# regulator_plus_switch_multi_no_rdbk.net
KiCad netlist of a schematic drawn in EAGLE
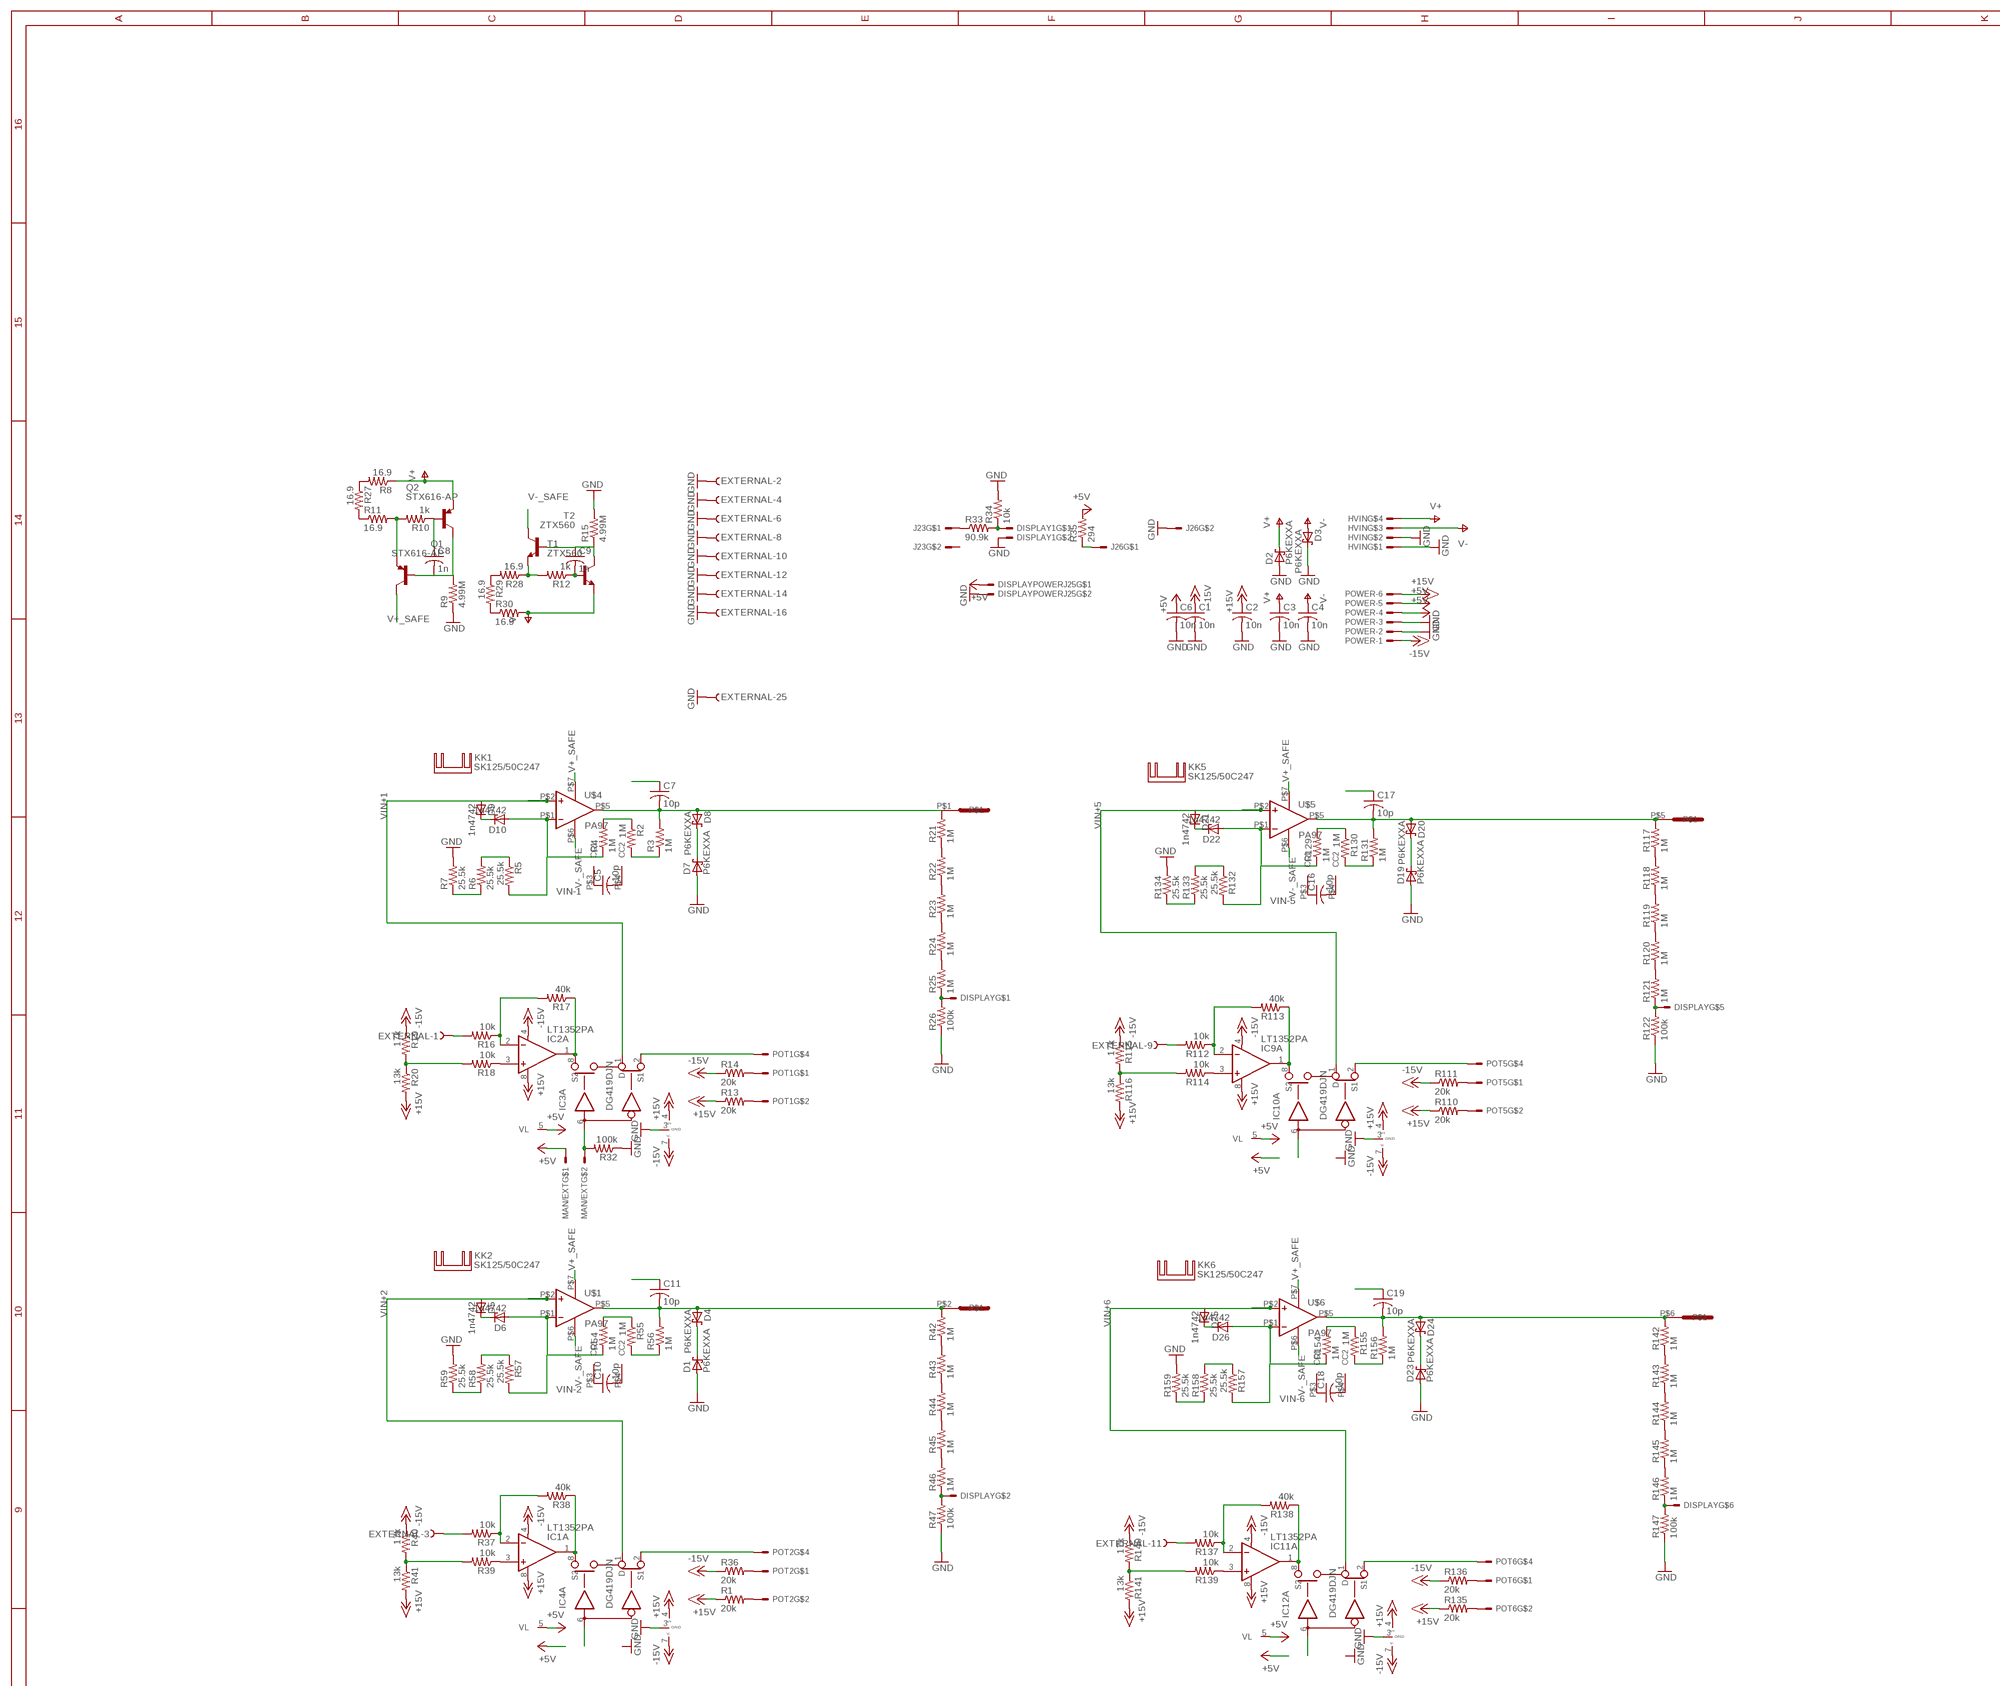
[diagram p0: schematic, sheet 1, part 1 of 2]
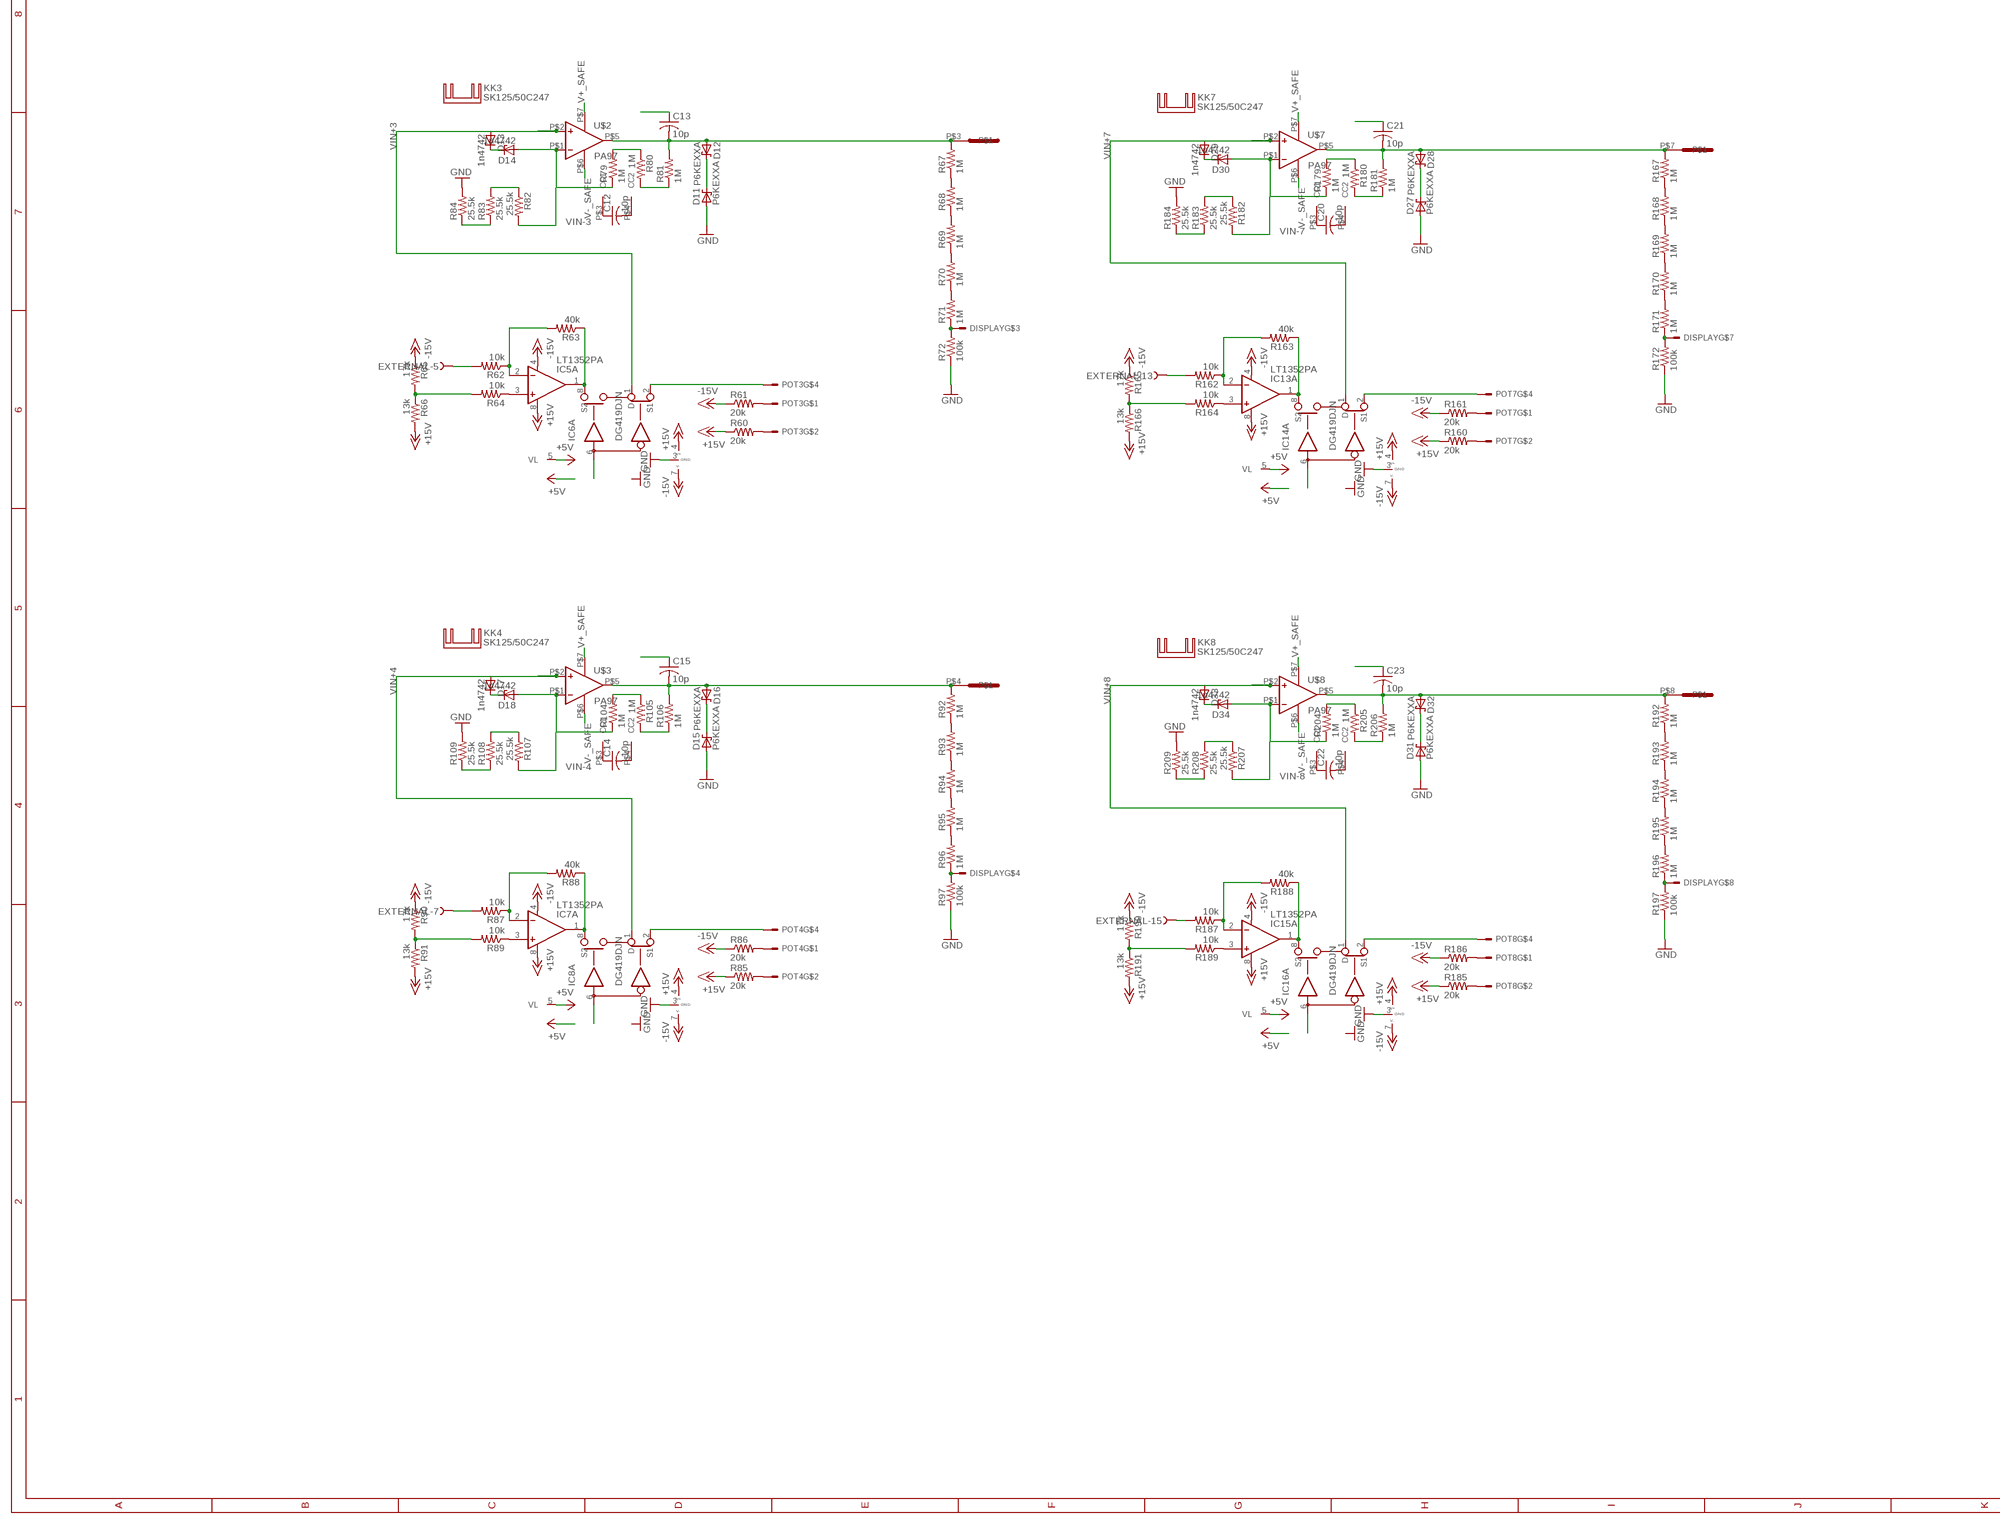
[diagram p1: schematic, sheet 1, part 2 of 2]

(export (version "E")
  (design (tool "Eeschema 10.0.6"))
  (components
    (comp (ref "C1")
      (value "10n")
      (footprint "eagle-import:C075-032X103")
      (libsource (lib "eagle-import") (part "C-US075-032X103"))
    )
    (comp (ref "C2")
      (value "10n")
      (footprint "eagle-import:C075-032X103")
      (libsource (lib "eagle-import") (part "C-US075-032X103"))
    )
    (comp (ref "C3")
      (value "10n")
      (footprint "eagle-import:C075-032X103")
      (libsource (lib "eagle-import") (part "C-US075-032X103"))
    )
    (comp (ref "C4")
      (value "10n")
      (footprint "eagle-import:C075-032X103")
      (libsource (lib "eagle-import") (part "C-US075-032X103"))
    )
    (comp (ref "C5")
      (value "10p")
      (footprint "eagle-import:C075-032X103")
      (libsource (lib "eagle-import") (part "C-US075-032X103"))
    )
    (comp (ref "C6")
      (value "10n")
      (footprint "eagle-import:C075-032X103")
      (libsource (lib "eagle-import") (part "C-US075-032X103"))
    )
    (comp (ref "C7")
      (value "10p")
      (footprint "eagle-import:C075-032X103")
      (libsource (lib "eagle-import") (part "C-US075-032X103"))
    )
    (comp (ref "C8")
      (value "1n")
      (footprint "eagle-import:C075-032X103")
      (libsource (lib "eagle-import") (part "C-US075-032X103"))
    )
    (comp (ref "C9")
      (value "1n")
      (footprint "eagle-import:C075-032X103")
      (libsource (lib "eagle-import") (part "C-US075-032X103"))
    )
    (comp (ref "C10")
      (value "10p")
      (footprint "eagle-import:C075-032X103")
      (libsource (lib "eagle-import") (part "C-US075-032X103"))
    )
    (comp (ref "C11")
      (value "10p")
      (footprint "eagle-import:C075-032X103")
      (libsource (lib "eagle-import") (part "C-US075-032X103"))
    )
    (comp (ref "C12")
      (value "10p")
      (footprint "eagle-import:C075-032X103")
      (libsource (lib "eagle-import") (part "C-US075-032X103"))
    )
    (comp (ref "C13")
      (value "10p")
      (footprint "eagle-import:C075-032X103")
      (libsource (lib "eagle-import") (part "C-US075-032X103"))
    )
    (comp (ref "C14")
      (value "10p")
      (footprint "eagle-import:C075-032X103")
      (libsource (lib "eagle-import") (part "C-US075-032X103"))
    )
    (comp (ref "C15")
      (value "10p")
      (footprint "eagle-import:C075-032X103")
      (libsource (lib "eagle-import") (part "C-US075-032X103"))
    )
    (comp (ref "C16")
      (value "10p")
      (footprint "eagle-import:C075-032X103")
      (libsource (lib "eagle-import") (part "C-US075-032X103"))
    )
    (comp (ref "C17")
      (value "10p")
      (footprint "eagle-import:C075-032X103")
      (libsource (lib "eagle-import") (part "C-US075-032X103"))
    )
    (comp (ref "C18")
      (value "10p")
      (footprint "eagle-import:C075-032X103")
      (libsource (lib "eagle-import") (part "C-US075-032X103"))
    )
    (comp (ref "C19")
      (value "10p")
      (footprint "eagle-import:C075-032X103")
      (libsource (lib "eagle-import") (part "C-US075-032X103"))
    )
    (comp (ref "C20")
      (value "10p")
      (footprint "eagle-import:C075-032X103")
      (libsource (lib "eagle-import") (part "C-US075-032X103"))
    )
    (comp (ref "C21")
      (value "10p")
      (footprint "eagle-import:C075-032X103")
      (libsource (lib "eagle-import") (part "C-US075-032X103"))
    )
    (comp (ref "C22")
      (value "10p")
      (footprint "eagle-import:C075-032X103")
      (libsource (lib "eagle-import") (part "C-US075-032X103"))
    )
    (comp (ref "C23")
      (value "10p")
      (footprint "eagle-import:C075-032X103")
      (libsource (lib "eagle-import") (part "C-US075-032X103"))
    )
    (comp (ref "D1")
      (value "P6KEXXA")
      (footprint "eagle-import:C1702-15")
      (libsource (lib "eagle-import") (part "P6KEXXA"))
    )
    (comp (ref "D2")
      (value "P6KEXXA")
      (footprint "eagle-import:C1702-15")
      (libsource (lib "eagle-import") (part "P6KEXXA"))
    )
    (comp (ref "D3")
      (value "P6KEXXA")
      (footprint "eagle-import:C1702-15")
      (libsource (lib "eagle-import") (part "P6KEXXA"))
    )
    (comp (ref "D4")
      (value "P6KEXXA")
      (footprint "eagle-import:C1702-15")
      (libsource (lib "eagle-import") (part "P6KEXXA"))
    )
    (comp (ref "D5")
      (value "1n4742")
      (footprint "eagle-import:DO41Z10")
      (libsource (lib "eagle-import") (part "ZENER-DIODEDO41Z10"))
    )
    (comp (ref "D6")
      (value "1n4742")
      (footprint "eagle-import:DO41Z10")
      (libsource (lib "eagle-import") (part "ZENER-DIODEDO41Z10"))
    )
    (comp (ref "D7")
      (value "P6KEXXA")
      (footprint "eagle-import:C1702-15")
      (libsource (lib "eagle-import") (part "P6KEXXA"))
    )
    (comp (ref "D8")
      (value "P6KEXXA")
      (footprint "eagle-import:C1702-15")
      (libsource (lib "eagle-import") (part "P6KEXXA"))
    )
    (comp (ref "D9")
      (value "1n4742")
      (footprint "eagle-import:DO41Z10")
      (libsource (lib "eagle-import") (part "ZENER-DIODEDO41Z10"))
    )
    (comp (ref "D10")
      (value "1n4742")
      (footprint "eagle-import:DO41Z10")
      (libsource (lib "eagle-import") (part "ZENER-DIODEDO41Z10"))
    )
    (comp (ref "D11")
      (value "P6KEXXA")
      (footprint "eagle-import:C1702-15")
      (libsource (lib "eagle-import") (part "P6KEXXA"))
    )
    (comp (ref "D12")
      (value "P6KEXXA")
      (footprint "eagle-import:C1702-15")
      (libsource (lib "eagle-import") (part "P6KEXXA"))
    )
    (comp (ref "D13")
      (value "1n4742")
      (footprint "eagle-import:DO41Z10")
      (libsource (lib "eagle-import") (part "ZENER-DIODEDO41Z10"))
    )
    (comp (ref "D14")
      (value "1n4742")
      (footprint "eagle-import:DO41Z10")
      (libsource (lib "eagle-import") (part "ZENER-DIODEDO41Z10"))
    )
    (comp (ref "D15")
      (value "P6KEXXA")
      (footprint "eagle-import:C1702-15")
      (libsource (lib "eagle-import") (part "P6KEXXA"))
    )
    (comp (ref "D16")
      (value "P6KEXXA")
      (footprint "eagle-import:C1702-15")
      (libsource (lib "eagle-import") (part "P6KEXXA"))
    )
    (comp (ref "D17")
      (value "1n4742")
      (footprint "eagle-import:DO41Z10")
      (libsource (lib "eagle-import") (part "ZENER-DIODEDO41Z10"))
    )
    (comp (ref "D18")
      (value "1n4742")
      (footprint "eagle-import:DO41Z10")
      (libsource (lib "eagle-import") (part "ZENER-DIODEDO41Z10"))
    )
    (comp (ref "D19")
      (value "P6KEXXA")
      (footprint "eagle-import:C1702-15")
      (libsource (lib "eagle-import") (part "P6KEXXA"))
    )
    (comp (ref "D20")
      (value "P6KEXXA")
      (footprint "eagle-import:C1702-15")
      (libsource (lib "eagle-import") (part "P6KEXXA"))
    )
    (comp (ref "D21")
      (value "1n4742")
      (footprint "eagle-import:DO41Z10")
      (libsource (lib "eagle-import") (part "ZENER-DIODEDO41Z10"))
    )
    (comp (ref "D22")
      (value "1n4742")
      (footprint "eagle-import:DO41Z10")
      (libsource (lib "eagle-import") (part "ZENER-DIODEDO41Z10"))
    )
    (comp (ref "D23")
      (value "P6KEXXA")
      (footprint "eagle-import:C1702-15")
      (libsource (lib "eagle-import") (part "P6KEXXA"))
    )
    (comp (ref "D24")
      (value "P6KEXXA")
      (footprint "eagle-import:C1702-15")
      (libsource (lib "eagle-import") (part "P6KEXXA"))
    )
    (comp (ref "D25")
      (value "1n4742")
      (footprint "eagle-import:DO41Z10")
      (libsource (lib "eagle-import") (part "ZENER-DIODEDO41Z10"))
    )
    (comp (ref "D26")
      (value "1n4742")
      (footprint "eagle-import:DO41Z10")
      (libsource (lib "eagle-import") (part "ZENER-DIODEDO41Z10"))
    )
    (comp (ref "D27")
      (value "P6KEXXA")
      (footprint "eagle-import:C1702-15")
      (libsource (lib "eagle-import") (part "P6KEXXA"))
    )
    (comp (ref "D28")
      (value "P6KEXXA")
      (footprint "eagle-import:C1702-15")
      (libsource (lib "eagle-import") (part "P6KEXXA"))
    )
    (comp (ref "D29")
      (value "1n4742")
      (footprint "eagle-import:DO41Z10")
      (libsource (lib "eagle-import") (part "ZENER-DIODEDO41Z10"))
    )
    (comp (ref "D30")
      (value "1n4742")
      (footprint "eagle-import:DO41Z10")
      (libsource (lib "eagle-import") (part "ZENER-DIODEDO41Z10"))
    )
    (comp (ref "D31")
      (value "P6KEXXA")
      (footprint "eagle-import:C1702-15")
      (libsource (lib "eagle-import") (part "P6KEXXA"))
    )
    (comp (ref "D32")
      (value "P6KEXXA")
      (footprint "eagle-import:C1702-15")
      (libsource (lib "eagle-import") (part "P6KEXXA"))
    )
    (comp (ref "D33")
      (value "1n4742")
      (footprint "eagle-import:DO41Z10")
      (libsource (lib "eagle-import") (part "ZENER-DIODEDO41Z10"))
    )
    (comp (ref "D34")
      (value "1n4742")
      (footprint "eagle-import:DO41Z10")
      (libsource (lib "eagle-import") (part "ZENER-DIODEDO41Z10"))
    )
    (comp (ref "DISPLAY")
      (value "5669-8")
      (footprint "eagle-import:5669-8")
      (libsource (lib "eagle-import") (part "5669-8"))
    )
    (comp (ref "DISPLAY1")
      (value "5569-2")
      (footprint "eagle-import:5569-2")
      (libsource (lib "eagle-import") (part "5569-2"))
    )
    (comp (ref "DISPLAYPOWERJ25")
      (value "5569-2")
      (footprint "eagle-import:5569-2")
      (libsource (lib "eagle-import") (part "5569-2"))
    )
    (comp (ref "EXTERNAL")
      (value "F25HPS")
      (footprint "eagle-import:F25HP")
      (libsource (lib "eagle-import") (part "F25?SHP"))
    )
    (comp (ref "HVIN")
      (value "5569-4")
      (footprint "eagle-import:5669-4")
      (libsource (lib "eagle-import") (part "5569-4"))
    )
    (comp (ref "IC1")
      (value "LT1352PA")
      (footprint "eagle-import:DIL08")
      (libsource (lib "eagle-import") (part "LT1352PA"))
    )
    (comp (ref "IC2")
      (value "LT1352PA")
      (footprint "eagle-import:DIL08")
      (libsource (lib "eagle-import") (part "LT1352PA"))
    )
    (comp (ref "IC3")
      (value "DG419DJN")
      (footprint "eagle-import:DIL08")
      (libsource (lib "eagle-import") (part "DG419DJN"))
    )
    (comp (ref "IC4")
      (value "DG419DJN")
      (footprint "eagle-import:DIL08")
      (libsource (lib "eagle-import") (part "DG419DJN"))
    )
    (comp (ref "IC5")
      (value "LT1352PA")
      (footprint "eagle-import:DIL08")
      (libsource (lib "eagle-import") (part "LT1352PA"))
    )
    (comp (ref "IC6")
      (value "DG419DJN")
      (footprint "eagle-import:DIL08")
      (libsource (lib "eagle-import") (part "DG419DJN"))
    )
    (comp (ref "IC7")
      (value "LT1352PA")
      (footprint "eagle-import:DIL08")
      (libsource (lib "eagle-import") (part "LT1352PA"))
    )
    (comp (ref "IC8")
      (value "DG419DJN")
      (footprint "eagle-import:DIL08")
      (libsource (lib "eagle-import") (part "DG419DJN"))
    )
    (comp (ref "IC9")
      (value "LT1352PA")
      (footprint "eagle-import:DIL08")
      (libsource (lib "eagle-import") (part "LT1352PA"))
    )
    (comp (ref "IC10")
      (value "DG419DJN")
      (footprint "eagle-import:DIL08")
      (libsource (lib "eagle-import") (part "DG419DJN"))
    )
    (comp (ref "IC11")
      (value "LT1352PA")
      (footprint "eagle-import:DIL08")
      (libsource (lib "eagle-import") (part "LT1352PA"))
    )
    (comp (ref "IC12")
      (value "DG419DJN")
      (footprint "eagle-import:DIL08")
      (libsource (lib "eagle-import") (part "DG419DJN"))
    )
    (comp (ref "IC13")
      (value "LT1352PA")
      (footprint "eagle-import:DIL08")
      (libsource (lib "eagle-import") (part "LT1352PA"))
    )
    (comp (ref "IC14")
      (value "DG419DJN")
      (footprint "eagle-import:DIL08")
      (libsource (lib "eagle-import") (part "DG419DJN"))
    )
    (comp (ref "IC15")
      (value "LT1352PA")
      (footprint "eagle-import:DIL08")
      (libsource (lib "eagle-import") (part "LT1352PA"))
    )
    (comp (ref "IC16")
      (value "DG419DJN")
      (footprint "eagle-import:DIL08")
      (libsource (lib "eagle-import") (part "DG419DJN"))
    )
    (comp (ref "J23")
      (value "5569-2")
      (footprint "eagle-import:5569-2")
      (libsource (lib "eagle-import") (part "5569-2"))
    )
    (comp (ref "J26")
      (value "5569-2")
      (footprint "eagle-import:5569-2")
      (libsource (lib "eagle-import") (part "5569-2"))
    )
    (comp (ref "KK1")
      (value "SK125/50C247")
      (footprint "eagle-import:C247-050")
      (libsource (lib "eagle-import") (part "SK125/50C247"))
    )
    (comp (ref "KK2")
      (value "SK125/50C247")
      (footprint "eagle-import:C247-050")
      (libsource (lib "eagle-import") (part "SK125/50C247"))
    )
    (comp (ref "KK3")
      (value "SK125/50C247")
      (footprint "eagle-import:C247-050")
      (libsource (lib "eagle-import") (part "SK125/50C247"))
    )
    (comp (ref "KK4")
      (value "SK125/50C247")
      (footprint "eagle-import:C247-050")
      (libsource (lib "eagle-import") (part "SK125/50C247"))
    )
    (comp (ref "KK5")
      (value "SK125/50C247")
      (footprint "eagle-import:C247-050")
      (libsource (lib "eagle-import") (part "SK125/50C247"))
    )
    (comp (ref "KK6")
      (value "SK125/50C247")
      (footprint "eagle-import:C247-050")
      (libsource (lib "eagle-import") (part "SK125/50C247"))
    )
    (comp (ref "KK7")
      (value "SK125/50C247")
      (footprint "eagle-import:C247-050")
      (libsource (lib "eagle-import") (part "SK125/50C247"))
    )
    (comp (ref "KK8")
      (value "SK125/50C247")
      (footprint "eagle-import:C247-050")
      (libsource (lib "eagle-import") (part "SK125/50C247"))
    )
    (comp (ref "MAN/EXT")
      (value "5569-2")
      (footprint "eagle-import:5569-2")
      (libsource (lib "eagle-import") (part "5569-2"))
    )
    (comp (ref "OUT")
      (value "640584-1")
      (footprint "eagle-import:640584-1")
      (libsource (lib "eagle-import") (part "640584-1"))
    )
    (comp (ref "POT1")
      (value "5569-4")
      (footprint "eagle-import:5669-4")
      (libsource (lib "eagle-import") (part "5569-4"))
    )
    (comp (ref "POT2")
      (value "5569-4")
      (footprint "eagle-import:5669-4")
      (libsource (lib "eagle-import") (part "5569-4"))
    )
    (comp (ref "POT3")
      (value "5569-4")
      (footprint "eagle-import:5669-4")
      (libsource (lib "eagle-import") (part "5569-4"))
    )
    (comp (ref "POT4")
      (value "5569-4")
      (footprint "eagle-import:5669-4")
      (libsource (lib "eagle-import") (part "5569-4"))
    )
    (comp (ref "POT5")
      (value "5569-4")
      (footprint "eagle-import:5669-4")
      (libsource (lib "eagle-import") (part "5569-4"))
    )
    (comp (ref "POT6")
      (value "5569-4")
      (footprint "eagle-import:5669-4")
      (libsource (lib "eagle-import") (part "5569-4"))
    )
    (comp (ref "POT7")
      (value "5569-4")
      (footprint "eagle-import:5669-4")
      (libsource (lib "eagle-import") (part "5569-4"))
    )
    (comp (ref "POT8")
      (value "5569-4")
      (footprint "eagle-import:5669-4")
      (libsource (lib "eagle-import") (part "5569-4"))
    )
    (comp (ref "POWER")
      (value "KK-156-6")
      (footprint "eagle-import:KK-156-6")
      (libsource (lib "eagle-import") (part "KK-156-6"))
    )
    (comp (ref "Q1")
      (value "STX616-AP")
      (footprint "eagle-import:TO92L")
      (libsource (lib "eagle-import") (part "2N3906L"))
    )
    (comp (ref "Q2")
      (value "STX616-AP")
      (footprint "eagle-import:TO92L")
      (libsource (lib "eagle-import") (part "2N3906L"))
    )
    (comp (ref "R1")
      (value "20k")
      (footprint "eagle-import:0207_10")
      (libsource (lib "eagle-import") (part "R-US_0207/10"))
    )
    (comp (ref "R2")
      (value "1M")
      (footprint "eagle-import:0207_10")
      (libsource (lib "eagle-import") (part "R-US_0207/10"))
    )
    (comp (ref "R3")
      (value "1M")
      (footprint "eagle-import:0207_10")
      (libsource (lib "eagle-import") (part "R-US_0207/10"))
    )
    (comp (ref "R4")
      (value "1M")
      (footprint "eagle-import:0207_10")
      (libsource (lib "eagle-import") (part "R-US_0207/10"))
    )
    (comp (ref "R5")
      (value "25.5k")
      (footprint "eagle-import:0207_10")
      (libsource (lib "eagle-import") (part "R-US_0207/10"))
    )
    (comp (ref "R6")
      (value "25.5k")
      (footprint "eagle-import:0207_10")
      (libsource (lib "eagle-import") (part "R-US_0207/10"))
    )
    (comp (ref "R7")
      (value "25.5k")
      (footprint "eagle-import:0207_10")
      (libsource (lib "eagle-import") (part "R-US_0207/10"))
    )
    (comp (ref "R8")
      (value "16.9")
      (footprint "eagle-import:0207_10")
      (libsource (lib "eagle-import") (part "R-US_0207/10"))
    )
    (comp (ref "R9")
      (value "4.99M")
      (footprint "eagle-import:0207_10")
      (libsource (lib "eagle-import") (part "R-US_0207/10"))
    )
    (comp (ref "R10")
      (value "1k")
      (footprint "eagle-import:0207_10")
      (libsource (lib "eagle-import") (part "R-US_0207/10"))
    )
    (comp (ref "R11")
      (value "16.9")
      (footprint "eagle-import:0207_10")
      (libsource (lib "eagle-import") (part "R-US_0207/10"))
    )
    (comp (ref "R12")
      (value "1k")
      (footprint "eagle-import:0207_10")
      (libsource (lib "eagle-import") (part "R-US_0207/10"))
    )
    (comp (ref "R13")
      (value "20k")
      (footprint "eagle-import:0207_10")
      (libsource (lib "eagle-import") (part "R-US_0207/10"))
    )
    (comp (ref "R14")
      (value "20k")
      (footprint "eagle-import:0207_10")
      (libsource (lib "eagle-import") (part "R-US_0207/10"))
    )
    (comp (ref "R15")
      (value "4.99M")
      (footprint "eagle-import:0207_10")
      (libsource (lib "eagle-import") (part "R-US_0207/10"))
    )
    (comp (ref "R16")
      (value "10k")
      (footprint "eagle-import:0207_10")
      (libsource (lib "eagle-import") (part "R-US_0207/10"))
    )
    (comp (ref "R17")
      (value "40k")
      (footprint "eagle-import:0207_10")
      (libsource (lib "eagle-import") (part "R-US_0207/10"))
    )
    (comp (ref "R18")
      (value "10k")
      (footprint "eagle-import:0207_10")
      (libsource (lib "eagle-import") (part "R-US_0207/10"))
    )
    (comp (ref "R19")
      (value "17k")
      (footprint "eagle-import:0207_10")
      (libsource (lib "eagle-import") (part "R-US_0207/10"))
    )
    (comp (ref "R20")
      (value "13k")
      (footprint "eagle-import:0207_10")
      (libsource (lib "eagle-import") (part "R-US_0207/10"))
    )
    (comp (ref "R21")
      (value "1M")
      (footprint "eagle-import:0207_10")
      (libsource (lib "eagle-import") (part "resistor_R-US_0207/10"))
    )
    (comp (ref "R22")
      (value "1M")
      (footprint "eagle-import:0207_10")
      (libsource (lib "eagle-import") (part "resistor_R-US_0207/10"))
    )
    (comp (ref "R23")
      (value "1M")
      (footprint "eagle-import:0207_10")
      (libsource (lib "eagle-import") (part "resistor_R-US_0207/10"))
    )
    (comp (ref "R24")
      (value "1M")
      (footprint "eagle-import:0207_10")
      (libsource (lib "eagle-import") (part "resistor_R-US_0207/10"))
    )
    (comp (ref "R25")
      (value "1M")
      (footprint "eagle-import:0207_10")
      (libsource (lib "eagle-import") (part "resistor_R-US_0207/10"))
    )
    (comp (ref "R26")
      (value "100k")
      (footprint "eagle-import:0207_10")
      (libsource (lib "eagle-import") (part "R-US_0207/10"))
    )
    (comp (ref "R27")
      (value "16.9")
      (footprint "eagle-import:0207_10")
      (libsource (lib "eagle-import") (part "R-US_0207/10"))
    )
    (comp (ref "R28")
      (value "16.9")
      (footprint "eagle-import:0207_10")
      (libsource (lib "eagle-import") (part "R-US_0207/10"))
    )
    (comp (ref "R29")
      (value "16.9")
      (footprint "eagle-import:0207_10")
      (libsource (lib "eagle-import") (part "R-US_0207/10"))
    )
    (comp (ref "R30")
      (value "16.9")
      (footprint "eagle-import:0207_10")
      (libsource (lib "eagle-import") (part "R-US_0207/10"))
    )
    (comp (ref "R32")
      (value "100k")
      (footprint "eagle-import:0207_10")
      (libsource (lib "eagle-import") (part "R-US_0207/10"))
    )
    (comp (ref "R33")
      (value "90.9k")
      (footprint "eagle-import:0207_10")
      (libsource (lib "eagle-import") (part "R-US_0207/10"))
    )
    (comp (ref "R34")
      (value "10k")
      (footprint "eagle-import:0207_10")
      (libsource (lib "eagle-import") (part "R-US_0207/10"))
    )
    (comp (ref "R35")
      (value "294")
      (footprint "eagle-import:0207_10")
      (libsource (lib "eagle-import") (part "R-US_0207/10"))
    )
    (comp (ref "R36")
      (value "20k")
      (footprint "eagle-import:0207_10")
      (libsource (lib "eagle-import") (part "R-US_0207/10"))
    )
    (comp (ref "R37")
      (value "10k")
      (footprint "eagle-import:0207_10")
      (libsource (lib "eagle-import") (part "R-US_0207/10"))
    )
    (comp (ref "R38")
      (value "40k")
      (footprint "eagle-import:0207_10")
      (libsource (lib "eagle-import") (part "R-US_0207/10"))
    )
    (comp (ref "R39")
      (value "10k")
      (footprint "eagle-import:0207_10")
      (libsource (lib "eagle-import") (part "R-US_0207/10"))
    )
    (comp (ref "R40")
      (value "17k")
      (footprint "eagle-import:0207_10")
      (libsource (lib "eagle-import") (part "R-US_0207/10"))
    )
    (comp (ref "R41")
      (value "13k")
      (footprint "eagle-import:0207_10")
      (libsource (lib "eagle-import") (part "R-US_0207/10"))
    )
    (comp (ref "R42")
      (value "1M")
      (footprint "eagle-import:0207_10")
      (libsource (lib "eagle-import") (part "resistor_R-US_0207/10"))
    )
    (comp (ref "R43")
      (value "1M")
      (footprint "eagle-import:0207_10")
      (libsource (lib "eagle-import") (part "resistor_R-US_0207/10"))
    )
    (comp (ref "R44")
      (value "1M")
      (footprint "eagle-import:0207_10")
      (libsource (lib "eagle-import") (part "resistor_R-US_0207/10"))
    )
    (comp (ref "R45")
      (value "1M")
      (footprint "eagle-import:0207_10")
      (libsource (lib "eagle-import") (part "resistor_R-US_0207/10"))
    )
    (comp (ref "R46")
      (value "1M")
      (footprint "eagle-import:0207_10")
      (libsource (lib "eagle-import") (part "resistor_R-US_0207/10"))
    )
    (comp (ref "R47")
      (value "100k")
      (footprint "eagle-import:0207_10")
      (libsource (lib "eagle-import") (part "R-US_0207/10"))
    )
    (comp (ref "R54")
      (value "1M")
      (footprint "eagle-import:0207_10")
      (libsource (lib "eagle-import") (part "R-US_0207/10"))
    )
    (comp (ref "R55")
      (value "1M")
      (footprint "eagle-import:0207_10")
      (libsource (lib "eagle-import") (part "R-US_0207/10"))
    )
    (comp (ref "R56")
      (value "1M")
      (footprint "eagle-import:0207_10")
      (libsource (lib "eagle-import") (part "R-US_0207/10"))
    )
    (comp (ref "R57")
      (value "25.5k")
      (footprint "eagle-import:0207_10")
      (libsource (lib "eagle-import") (part "R-US_0207/10"))
    )
    (comp (ref "R58")
      (value "25.5k")
      (footprint "eagle-import:0207_10")
      (libsource (lib "eagle-import") (part "R-US_0207/10"))
    )
    (comp (ref "R59")
      (value "25.5k")
      (footprint "eagle-import:0207_10")
      (libsource (lib "eagle-import") (part "R-US_0207/10"))
    )
    (comp (ref "R60")
      (value "20k")
      (footprint "eagle-import:0207_10")
      (libsource (lib "eagle-import") (part "R-US_0207/10"))
    )
    (comp (ref "R61")
      (value "20k")
      (footprint "eagle-import:0207_10")
      (libsource (lib "eagle-import") (part "R-US_0207/10"))
    )
    (comp (ref "R62")
      (value "10k")
      (footprint "eagle-import:0207_10")
      (libsource (lib "eagle-import") (part "R-US_0207/10"))
    )
    (comp (ref "R63")
      (value "40k")
      (footprint "eagle-import:0207_10")
      (libsource (lib "eagle-import") (part "R-US_0207/10"))
    )
    (comp (ref "R64")
      (value "10k")
      (footprint "eagle-import:0207_10")
      (libsource (lib "eagle-import") (part "R-US_0207/10"))
    )
    (comp (ref "R65")
      (value "17k")
      (footprint "eagle-import:0207_10")
      (libsource (lib "eagle-import") (part "R-US_0207/10"))
    )
    (comp (ref "R66")
      (value "13k")
      (footprint "eagle-import:0207_10")
      (libsource (lib "eagle-import") (part "R-US_0207/10"))
    )
    (comp (ref "R67")
      (value "1M")
      (footprint "eagle-import:0207_10")
      (libsource (lib "eagle-import") (part "resistor_R-US_0207/10"))
    )
    (comp (ref "R68")
      (value "1M")
      (footprint "eagle-import:0207_10")
      (libsource (lib "eagle-import") (part "resistor_R-US_0207/10"))
    )
    (comp (ref "R69")
      (value "1M")
      (footprint "eagle-import:0207_10")
      (libsource (lib "eagle-import") (part "resistor_R-US_0207/10"))
    )
    (comp (ref "R70")
      (value "1M")
      (footprint "eagle-import:0207_10")
      (libsource (lib "eagle-import") (part "resistor_R-US_0207/10"))
    )
    (comp (ref "R71")
      (value "1M")
      (footprint "eagle-import:0207_10")
      (libsource (lib "eagle-import") (part "resistor_R-US_0207/10"))
    )
    (comp (ref "R72")
      (value "100k")
      (footprint "eagle-import:0207_10")
      (libsource (lib "eagle-import") (part "R-US_0207/10"))
    )
    (comp (ref "R79")
      (value "1M")
      (footprint "eagle-import:0207_10")
      (libsource (lib "eagle-import") (part "R-US_0207/10"))
    )
    (comp (ref "R80")
      (value "1M")
      (footprint "eagle-import:0207_10")
      (libsource (lib "eagle-import") (part "R-US_0207/10"))
    )
    (comp (ref "R81")
      (value "1M")
      (footprint "eagle-import:0207_10")
      (libsource (lib "eagle-import") (part "R-US_0207/10"))
    )
    (comp (ref "R82")
      (value "25.5k")
      (footprint "eagle-import:0207_10")
      (libsource (lib "eagle-import") (part "R-US_0207/10"))
    )
    (comp (ref "R83")
      (value "25.5k")
      (footprint "eagle-import:0207_10")
      (libsource (lib "eagle-import") (part "R-US_0207/10"))
    )
    (comp (ref "R84")
      (value "25.5k")
      (footprint "eagle-import:0207_10")
      (libsource (lib "eagle-import") (part "R-US_0207/10"))
    )
    (comp (ref "R85")
      (value "20k")
      (footprint "eagle-import:0207_10")
      (libsource (lib "eagle-import") (part "R-US_0207/10"))
    )
    (comp (ref "R86")
      (value "20k")
      (footprint "eagle-import:0207_10")
      (libsource (lib "eagle-import") (part "R-US_0207/10"))
    )
    (comp (ref "R87")
      (value "10k")
      (footprint "eagle-import:0207_10")
      (libsource (lib "eagle-import") (part "R-US_0207/10"))
    )
    (comp (ref "R88")
      (value "40k")
      (footprint "eagle-import:0207_10")
      (libsource (lib "eagle-import") (part "R-US_0207/10"))
    )
    (comp (ref "R89")
      (value "10k")
      (footprint "eagle-import:0207_10")
      (libsource (lib "eagle-import") (part "R-US_0207/10"))
    )
    (comp (ref "R90")
      (value "17k")
      (footprint "eagle-import:0207_10")
      (libsource (lib "eagle-import") (part "R-US_0207/10"))
    )
    (comp (ref "R91")
      (value "13k")
      (footprint "eagle-import:0207_10")
      (libsource (lib "eagle-import") (part "R-US_0207/10"))
    )
    (comp (ref "R92")
      (value "1M")
      (footprint "eagle-import:0207_10")
      (libsource (lib "eagle-import") (part "resistor_R-US_0207/10"))
    )
    (comp (ref "R93")
      (value "1M")
      (footprint "eagle-import:0207_10")
      (libsource (lib "eagle-import") (part "resistor_R-US_0207/10"))
    )
    (comp (ref "R94")
      (value "1M")
      (footprint "eagle-import:0207_10")
      (libsource (lib "eagle-import") (part "resistor_R-US_0207/10"))
    )
    (comp (ref "R95")
      (value "1M")
      (footprint "eagle-import:0207_10")
      (libsource (lib "eagle-import") (part "resistor_R-US_0207/10"))
    )
    (comp (ref "R96")
      (value "1M")
      (footprint "eagle-import:0207_10")
      (libsource (lib "eagle-import") (part "resistor_R-US_0207/10"))
    )
    (comp (ref "R97")
      (value "100k")
      (footprint "eagle-import:0207_10")
      (libsource (lib "eagle-import") (part "R-US_0207/10"))
    )
    (comp (ref "R104")
      (value "1M")
      (footprint "eagle-import:0207_10")
      (libsource (lib "eagle-import") (part "R-US_0207/10"))
    )
    (comp (ref "R105")
      (value "1M")
      (footprint "eagle-import:0207_10")
      (libsource (lib "eagle-import") (part "R-US_0207/10"))
    )
    (comp (ref "R106")
      (value "1M")
      (footprint "eagle-import:0207_10")
      (libsource (lib "eagle-import") (part "R-US_0207/10"))
    )
    (comp (ref "R107")
      (value "25.5k")
      (footprint "eagle-import:0207_10")
      (libsource (lib "eagle-import") (part "R-US_0207/10"))
    )
    (comp (ref "R108")
      (value "25.5k")
      (footprint "eagle-import:0207_10")
      (libsource (lib "eagle-import") (part "R-US_0207/10"))
    )
    (comp (ref "R109")
      (value "25.5k")
      (footprint "eagle-import:0207_10")
      (libsource (lib "eagle-import") (part "R-US_0207/10"))
    )
    (comp (ref "R110")
      (value "20k")
      (footprint "eagle-import:0207_10")
      (libsource (lib "eagle-import") (part "R-US_0207/10"))
    )
    (comp (ref "R111")
      (value "20k")
      (footprint "eagle-import:0207_10")
      (libsource (lib "eagle-import") (part "R-US_0207/10"))
    )
    (comp (ref "R112")
      (value "10k")
      (footprint "eagle-import:0207_10")
      (libsource (lib "eagle-import") (part "R-US_0207/10"))
    )
    (comp (ref "R113")
      (value "40k")
      (footprint "eagle-import:0207_10")
      (libsource (lib "eagle-import") (part "R-US_0207/10"))
    )
    (comp (ref "R114")
      (value "10k")
      (footprint "eagle-import:0207_10")
      (libsource (lib "eagle-import") (part "R-US_0207/10"))
    )
    (comp (ref "R115")
      (value "17k")
      (footprint "eagle-import:0207_10")
      (libsource (lib "eagle-import") (part "R-US_0207/10"))
    )
    (comp (ref "R116")
      (value "13k")
      (footprint "eagle-import:0207_10")
      (libsource (lib "eagle-import") (part "R-US_0207/10"))
    )
    (comp (ref "R117")
      (value "1M")
      (footprint "eagle-import:0207_10")
      (libsource (lib "eagle-import") (part "resistor_R-US_0207/10"))
    )
    (comp (ref "R118")
      (value "1M")
      (footprint "eagle-import:0207_10")
      (libsource (lib "eagle-import") (part "resistor_R-US_0207/10"))
    )
    (comp (ref "R119")
      (value "1M")
      (footprint "eagle-import:0207_10")
      (libsource (lib "eagle-import") (part "resistor_R-US_0207/10"))
    )
    (comp (ref "R120")
      (value "1M")
      (footprint "eagle-import:0207_10")
      (libsource (lib "eagle-import") (part "resistor_R-US_0207/10"))
    )
    (comp (ref "R121")
      (value "1M")
      (footprint "eagle-import:0207_10")
      (libsource (lib "eagle-import") (part "resistor_R-US_0207/10"))
    )
    (comp (ref "R122")
      (value "100k")
      (footprint "eagle-import:0207_10")
      (libsource (lib "eagle-import") (part "R-US_0207/10"))
    )
    (comp (ref "R129")
      (value "1M")
      (footprint "eagle-import:0207_10")
      (libsource (lib "eagle-import") (part "R-US_0207/10"))
    )
    (comp (ref "R130")
      (value "1M")
      (footprint "eagle-import:0207_10")
      (libsource (lib "eagle-import") (part "R-US_0207/10"))
    )
    (comp (ref "R131")
      (value "1M")
      (footprint "eagle-import:0207_10")
      (libsource (lib "eagle-import") (part "R-US_0207/10"))
    )
    (comp (ref "R132")
      (value "25.5k")
      (footprint "eagle-import:0207_10")
      (libsource (lib "eagle-import") (part "R-US_0207/10"))
    )
    (comp (ref "R133")
      (value "25.5k")
      (footprint "eagle-import:0207_10")
      (libsource (lib "eagle-import") (part "R-US_0207/10"))
    )
    (comp (ref "R134")
      (value "25.5k")
      (footprint "eagle-import:0207_10")
      (libsource (lib "eagle-import") (part "R-US_0207/10"))
    )
    (comp (ref "R135")
      (value "20k")
      (footprint "eagle-import:0207_10")
      (libsource (lib "eagle-import") (part "R-US_0207/10"))
    )
    (comp (ref "R136")
      (value "20k")
      (footprint "eagle-import:0207_10")
      (libsource (lib "eagle-import") (part "R-US_0207/10"))
    )
    (comp (ref "R137")
      (value "10k")
      (footprint "eagle-import:0207_10")
      (libsource (lib "eagle-import") (part "R-US_0207/10"))
    )
    (comp (ref "R138")
      (value "40k")
      (footprint "eagle-import:0207_10")
      (libsource (lib "eagle-import") (part "R-US_0207/10"))
    )
    (comp (ref "R139")
      (value "10k")
      (footprint "eagle-import:0207_10")
      (libsource (lib "eagle-import") (part "R-US_0207/10"))
    )
    (comp (ref "R140")
      (value "17k")
      (footprint "eagle-import:0207_10")
      (libsource (lib "eagle-import") (part "R-US_0207/10"))
    )
    (comp (ref "R141")
      (value "13k")
      (footprint "eagle-import:0207_10")
      (libsource (lib "eagle-import") (part "R-US_0207/10"))
    )
    (comp (ref "R142")
      (value "1M")
      (footprint "eagle-import:0207_10")
      (libsource (lib "eagle-import") (part "resistor_R-US_0207/10"))
    )
    (comp (ref "R143")
      (value "1M")
      (footprint "eagle-import:0207_10")
      (libsource (lib "eagle-import") (part "resistor_R-US_0207/10"))
    )
    (comp (ref "R144")
      (value "1M")
      (footprint "eagle-import:0207_10")
      (libsource (lib "eagle-import") (part "resistor_R-US_0207/10"))
    )
    (comp (ref "R145")
      (value "1M")
      (footprint "eagle-import:0207_10")
      (libsource (lib "eagle-import") (part "resistor_R-US_0207/10"))
    )
    (comp (ref "R146")
      (value "1M")
      (footprint "eagle-import:0207_10")
      (libsource (lib "eagle-import") (part "resistor_R-US_0207/10"))
    )
    (comp (ref "R147")
      (value "100k")
      (footprint "eagle-import:0207_10")
      (libsource (lib "eagle-import") (part "R-US_0207/10"))
    )
    (comp (ref "R154")
      (value "1M")
      (footprint "eagle-import:0207_10")
      (libsource (lib "eagle-import") (part "R-US_0207/10"))
    )
    (comp (ref "R155")
      (value "1M")
      (footprint "eagle-import:0207_10")
      (libsource (lib "eagle-import") (part "R-US_0207/10"))
    )
    (comp (ref "R156")
      (value "1M")
      (footprint "eagle-import:0207_10")
      (libsource (lib "eagle-import") (part "R-US_0207/10"))
    )
    (comp (ref "R157")
      (value "25.5k")
      (footprint "eagle-import:0207_10")
      (libsource (lib "eagle-import") (part "R-US_0207/10"))
    )
    (comp (ref "R158")
      (value "25.5k")
      (footprint "eagle-import:0207_10")
      (libsource (lib "eagle-import") (part "R-US_0207/10"))
    )
    (comp (ref "R159")
      (value "25.5k")
      (footprint "eagle-import:0207_10")
      (libsource (lib "eagle-import") (part "R-US_0207/10"))
    )
    (comp (ref "R160")
      (value "20k")
      (footprint "eagle-import:0207_10")
      (libsource (lib "eagle-import") (part "R-US_0207/10"))
    )
    (comp (ref "R161")
      (value "20k")
      (footprint "eagle-import:0207_10")
      (libsource (lib "eagle-import") (part "R-US_0207/10"))
    )
    (comp (ref "R162")
      (value "10k")
      (footprint "eagle-import:0207_10")
      (libsource (lib "eagle-import") (part "R-US_0207/10"))
    )
    (comp (ref "R163")
      (value "40k")
      (footprint "eagle-import:0207_10")
      (libsource (lib "eagle-import") (part "R-US_0207/10"))
    )
    (comp (ref "R164")
      (value "10k")
      (footprint "eagle-import:0207_10")
      (libsource (lib "eagle-import") (part "R-US_0207/10"))
    )
    (comp (ref "R165")
      (value "17k")
      (footprint "eagle-import:0207_10")
      (libsource (lib "eagle-import") (part "R-US_0207/10"))
    )
    (comp (ref "R166")
      (value "13k")
      (footprint "eagle-import:0207_10")
      (libsource (lib "eagle-import") (part "R-US_0207/10"))
    )
    (comp (ref "R167")
      (value "1M")
      (footprint "eagle-import:0207_10")
      (libsource (lib "eagle-import") (part "resistor_R-US_0207/10"))
    )
    (comp (ref "R168")
      (value "1M")
      (footprint "eagle-import:0207_10")
      (libsource (lib "eagle-import") (part "resistor_R-US_0207/10"))
    )
    (comp (ref "R169")
      (value "1M")
      (footprint "eagle-import:0207_10")
      (libsource (lib "eagle-import") (part "resistor_R-US_0207/10"))
    )
    (comp (ref "R170")
      (value "1M")
      (footprint "eagle-import:0207_10")
      (libsource (lib "eagle-import") (part "resistor_R-US_0207/10"))
    )
    (comp (ref "R171")
      (value "1M")
      (footprint "eagle-import:0207_10")
      (libsource (lib "eagle-import") (part "resistor_R-US_0207/10"))
    )
    (comp (ref "R172")
      (value "100k")
      (footprint "eagle-import:0207_10")
      (libsource (lib "eagle-import") (part "R-US_0207/10"))
    )
    (comp (ref "R179")
      (value "1M")
      (footprint "eagle-import:0207_10")
      (libsource (lib "eagle-import") (part "R-US_0207/10"))
    )
    (comp (ref "R180")
      (value "1M")
      (footprint "eagle-import:0207_10")
      (libsource (lib "eagle-import") (part "R-US_0207/10"))
    )
    (comp (ref "R181")
      (value "1M")
      (footprint "eagle-import:0207_10")
      (libsource (lib "eagle-import") (part "R-US_0207/10"))
    )
    (comp (ref "R182")
      (value "25.5k")
      (footprint "eagle-import:0207_10")
      (libsource (lib "eagle-import") (part "R-US_0207/10"))
    )
    (comp (ref "R183")
      (value "25.5k")
      (footprint "eagle-import:0207_10")
      (libsource (lib "eagle-import") (part "R-US_0207/10"))
    )
    (comp (ref "R184")
      (value "25.5k")
      (footprint "eagle-import:0207_10")
      (libsource (lib "eagle-import") (part "R-US_0207/10"))
    )
    (comp (ref "R185")
      (value "20k")
      (footprint "eagle-import:0207_10")
      (libsource (lib "eagle-import") (part "R-US_0207/10"))
    )
    (comp (ref "R186")
      (value "20k")
      (footprint "eagle-import:0207_10")
      (libsource (lib "eagle-import") (part "R-US_0207/10"))
    )
    (comp (ref "R187")
      (value "10k")
      (footprint "eagle-import:0207_10")
      (libsource (lib "eagle-import") (part "R-US_0207/10"))
    )
    (comp (ref "R188")
      (value "40k")
      (footprint "eagle-import:0207_10")
      (libsource (lib "eagle-import") (part "R-US_0207/10"))
    )
    (comp (ref "R189")
      (value "10k")
      (footprint "eagle-import:0207_10")
      (libsource (lib "eagle-import") (part "R-US_0207/10"))
    )
    (comp (ref "R190")
      (value "17k")
      (footprint "eagle-import:0207_10")
      (libsource (lib "eagle-import") (part "R-US_0207/10"))
    )
    (comp (ref "R191")
      (value "13k")
      (footprint "eagle-import:0207_10")
      (libsource (lib "eagle-import") (part "R-US_0207/10"))
    )
    (comp (ref "R192")
      (value "1M")
      (footprint "eagle-import:0207_10")
      (libsource (lib "eagle-import") (part "resistor_R-US_0207/10"))
    )
    (comp (ref "R193")
      (value "1M")
      (footprint "eagle-import:0207_10")
      (libsource (lib "eagle-import") (part "resistor_R-US_0207/10"))
    )
    (comp (ref "R194")
      (value "1M")
      (footprint "eagle-import:0207_10")
      (libsource (lib "eagle-import") (part "resistor_R-US_0207/10"))
    )
    (comp (ref "R195")
      (value "1M")
      (footprint "eagle-import:0207_10")
      (libsource (lib "eagle-import") (part "resistor_R-US_0207/10"))
    )
    (comp (ref "R196")
      (value "1M")
      (footprint "eagle-import:0207_10")
      (libsource (lib "eagle-import") (part "resistor_R-US_0207/10"))
    )
    (comp (ref "R197")
      (value "100k")
      (footprint "eagle-import:0207_10")
      (libsource (lib "eagle-import") (part "R-US_0207/10"))
    )
    (comp (ref "R204")
      (value "1M")
      (footprint "eagle-import:0207_10")
      (libsource (lib "eagle-import") (part "R-US_0207/10"))
    )
    (comp (ref "R205")
      (value "1M")
      (footprint "eagle-import:0207_10")
      (libsource (lib "eagle-import") (part "R-US_0207/10"))
    )
    (comp (ref "R206")
      (value "1M")
      (footprint "eagle-import:0207_10")
      (libsource (lib "eagle-import") (part "R-US_0207/10"))
    )
    (comp (ref "R207")
      (value "25.5k")
      (footprint "eagle-import:0207_10")
      (libsource (lib "eagle-import") (part "R-US_0207/10"))
    )
    (comp (ref "R208")
      (value "25.5k")
      (footprint "eagle-import:0207_10")
      (libsource (lib "eagle-import") (part "R-US_0207/10"))
    )
    (comp (ref "R209")
      (value "25.5k")
      (footprint "eagle-import:0207_10")
      (libsource (lib "eagle-import") (part "R-US_0207/10"))
    )
    (comp (ref "T1")
      (value "ZTX560")
      (footprint "eagle-import:TO92L")
      (libsource (lib "eagle-import") (part "2N3904L"))
    )
    (comp (ref "T2")
      (value "ZTX560")
      (footprint "eagle-import:TO92L")
      (libsource (lib "eagle-import") (part "2N3904L"))
    )
    (comp (ref "U$1")
      (value "PA97")
      (footprint "eagle-import:7SIP")
      (libsource (lib "eagle-import") (part "PA97"))
    )
    (comp (ref "U$2")
      (value "PA97")
      (footprint "eagle-import:7SIP")
      (libsource (lib "eagle-import") (part "PA97"))
    )
    (comp (ref "U$3")
      (value "PA97")
      (footprint "eagle-import:7SIP")
      (libsource (lib "eagle-import") (part "PA97"))
    )
    (comp (ref "U$4")
      (value "PA97")
      (footprint "eagle-import:7SIP")
      (libsource (lib "eagle-import") (part "PA97"))
    )
    (comp (ref "U$5")
      (value "PA97")
      (footprint "eagle-import:7SIP")
      (libsource (lib "eagle-import") (part "PA97"))
    )
    (comp (ref "U$6")
      (value "PA97")
      (footprint "eagle-import:7SIP")
      (libsource (lib "eagle-import") (part "PA97"))
    )
    (comp (ref "U$7")
      (value "PA97")
      (footprint "eagle-import:7SIP")
      (libsource (lib "eagle-import") (part "PA97"))
    )
    (comp (ref "U$8")
      (value "PA97")
      (footprint "eagle-import:7SIP")
      (libsource (lib "eagle-import") (part "PA97"))
    )
  )
  (nets
    (net (code "1") (name "+5V") (class "Default")
      (node (ref "C6") (pin "1") (pinfunction "1_1") (pintype "passive"))
      (node (ref "DISPLAYPOWERJ25") (pin "P$1") (pinfunction "S_P$1") (pintype "passive"))
      (node (ref "IC10") (pin "5") (pinfunction "VL_5") (pintype "input"))
      (node (ref "IC12") (pin "5") (pinfunction "VL_5") (pintype "input"))
      (node (ref "IC14") (pin "5") (pinfunction "VL_5") (pintype "input"))
      (node (ref "IC16") (pin "5") (pinfunction "VL_5") (pintype "input"))
      (node (ref "IC3") (pin "5") (pinfunction "VL_5") (pintype "input"))
      (node (ref "IC4") (pin "5") (pinfunction "VL_5") (pintype "input"))
      (node (ref "IC6") (pin "5") (pinfunction "VL_5") (pintype "input"))
      (node (ref "IC8") (pin "5") (pinfunction "VL_5") (pintype "input"))
      (node (ref "MAN/EXT") (pin "P$1") (pinfunction "S_P$1") (pintype "passive"))
      (node (ref "POWER") (pin "4") (pinfunction "S_4") (pintype "passive"))
      (node (ref "POWER") (pin "5") (pinfunction "S_5") (pintype "passive"))
      (node (ref "R35") (pin "2") (pinfunction "2_2") (pintype "passive"))
    )
    (net (code "2") (name "+15V") (class "Default")
      (node (ref "C2") (pin "1") (pinfunction "1_1") (pintype "passive"))
      (node (ref "IC1") (pin "8") (pinfunction "V+_8") (pintype "power_in"))
      (node (ref "IC10") (pin "4") (pinfunction "V+_4") (pintype "power_in"))
      (node (ref "IC11") (pin "8") (pinfunction "V+_8") (pintype "power_in"))
      (node (ref "IC12") (pin "4") (pinfunction "V+_4") (pintype "power_in"))
      (node (ref "IC13") (pin "8") (pinfunction "V+_8") (pintype "power_in"))
      (node (ref "IC14") (pin "4") (pinfunction "V+_4") (pintype "power_in"))
      (node (ref "IC15") (pin "8") (pinfunction "V+_8") (pintype "power_in"))
      (node (ref "IC16") (pin "4") (pinfunction "V+_4") (pintype "power_in"))
      (node (ref "IC2") (pin "8") (pinfunction "V+_8") (pintype "power_in"))
      (node (ref "IC3") (pin "4") (pinfunction "V+_4") (pintype "power_in"))
      (node (ref "IC4") (pin "4") (pinfunction "V+_4") (pintype "power_in"))
      (node (ref "IC5") (pin "8") (pinfunction "V+_8") (pintype "power_in"))
      (node (ref "IC6") (pin "4") (pinfunction "V+_4") (pintype "power_in"))
      (node (ref "IC7") (pin "8") (pinfunction "V+_8") (pintype "power_in"))
      (node (ref "IC8") (pin "4") (pinfunction "V+_4") (pintype "power_in"))
      (node (ref "IC9") (pin "8") (pinfunction "V+_8") (pintype "power_in"))
      (node (ref "POWER") (pin "6") (pinfunction "S_6") (pintype "passive"))
      (node (ref "R1") (pin "1") (pinfunction "1_1") (pintype "passive"))
      (node (ref "R110") (pin "1") (pinfunction "1_1") (pintype "passive"))
      (node (ref "R116") (pin "2") (pinfunction "2_2") (pintype "passive"))
      (node (ref "R13") (pin "1") (pinfunction "1_1") (pintype "passive"))
      (node (ref "R135") (pin "1") (pinfunction "1_1") (pintype "passive"))
      (node (ref "R141") (pin "2") (pinfunction "2_2") (pintype "passive"))
      (node (ref "R160") (pin "1") (pinfunction "1_1") (pintype "passive"))
      (node (ref "R166") (pin "2") (pinfunction "2_2") (pintype "passive"))
      (node (ref "R185") (pin "1") (pinfunction "1_1") (pintype "passive"))
      (node (ref "R191") (pin "2") (pinfunction "2_2") (pintype "passive"))
      (node (ref "R20") (pin "2") (pinfunction "2_2") (pintype "passive"))
      (node (ref "R41") (pin "2") (pinfunction "2_2") (pintype "passive"))
      (node (ref "R60") (pin "1") (pinfunction "1_1") (pintype "passive"))
      (node (ref "R66") (pin "2") (pinfunction "2_2") (pintype "passive"))
      (node (ref "R85") (pin "1") (pinfunction "1_1") (pintype "passive"))
      (node (ref "R91") (pin "2") (pinfunction "2_2") (pintype "passive"))
    )
    (net (code "3") (name "-15V") (class "Default")
      (node (ref "C1") (pin "1") (pinfunction "1_1") (pintype "passive"))
      (node (ref "IC1") (pin "4") (pinfunction "V-_4") (pintype "power_in"))
      (node (ref "IC10") (pin "7") (pinfunction "V-_7") (pintype "power_in"))
      (node (ref "IC11") (pin "4") (pinfunction "V-_4") (pintype "power_in"))
      (node (ref "IC12") (pin "7") (pinfunction "V-_7") (pintype "power_in"))
      (node (ref "IC13") (pin "4") (pinfunction "V-_4") (pintype "power_in"))
      (node (ref "IC14") (pin "7") (pinfunction "V-_7") (pintype "power_in"))
      (node (ref "IC15") (pin "4") (pinfunction "V-_4") (pintype "power_in"))
      (node (ref "IC16") (pin "7") (pinfunction "V-_7") (pintype "power_in"))
      (node (ref "IC2") (pin "4") (pinfunction "V-_4") (pintype "power_in"))
      (node (ref "IC3") (pin "7") (pinfunction "V-_7") (pintype "power_in"))
      (node (ref "IC4") (pin "7") (pinfunction "V-_7") (pintype "power_in"))
      (node (ref "IC5") (pin "4") (pinfunction "V-_4") (pintype "power_in"))
      (node (ref "IC6") (pin "7") (pinfunction "V-_7") (pintype "power_in"))
      (node (ref "IC7") (pin "4") (pinfunction "V-_4") (pintype "power_in"))
      (node (ref "IC8") (pin "7") (pinfunction "V-_7") (pintype "power_in"))
      (node (ref "IC9") (pin "4") (pinfunction "V-_4") (pintype "power_in"))
      (node (ref "POWER") (pin "1") (pinfunction "S_1") (pintype "passive"))
      (node (ref "R111") (pin "1") (pinfunction "1_1") (pintype "passive"))
      (node (ref "R115") (pin "1") (pinfunction "1_1") (pintype "passive"))
      (node (ref "R136") (pin "1") (pinfunction "1_1") (pintype "passive"))
      (node (ref "R14") (pin "1") (pinfunction "1_1") (pintype "passive"))
      (node (ref "R140") (pin "1") (pinfunction "1_1") (pintype "passive"))
      (node (ref "R161") (pin "1") (pinfunction "1_1") (pintype "passive"))
      (node (ref "R165") (pin "1") (pinfunction "1_1") (pintype "passive"))
      (node (ref "R186") (pin "1") (pinfunction "1_1") (pintype "passive"))
      (node (ref "R19") (pin "1") (pinfunction "1_1") (pintype "passive"))
      (node (ref "R190") (pin "1") (pinfunction "1_1") (pintype "passive"))
      (node (ref "R36") (pin "1") (pinfunction "1_1") (pintype "passive"))
      (node (ref "R40") (pin "1") (pinfunction "1_1") (pintype "passive"))
      (node (ref "R61") (pin "1") (pinfunction "1_1") (pintype "passive"))
      (node (ref "R65") (pin "1") (pinfunction "1_1") (pintype "passive"))
      (node (ref "R86") (pin "1") (pinfunction "1_1") (pintype "passive"))
      (node (ref "R90") (pin "1") (pinfunction "1_1") (pintype "passive"))
    )
    (net (code "4") (name "/MAN") (class "Default")
      (node (ref "IC10") (pin "6") (pinfunction "IN_6") (pintype "input"))
      (node (ref "IC12") (pin "6") (pinfunction "IN_6") (pintype "input"))
      (node (ref "IC14") (pin "6") (pinfunction "IN_6") (pintype "input"))
      (node (ref "IC16") (pin "6") (pinfunction "IN_6") (pintype "input"))
      (node (ref "IC3") (pin "6") (pinfunction "IN_6") (pintype "input"))
      (node (ref "IC4") (pin "6") (pinfunction "IN_6") (pintype "input"))
      (node (ref "IC6") (pin "6") (pinfunction "IN_6") (pintype "input"))
      (node (ref "IC8") (pin "6") (pinfunction "IN_6") (pintype "input"))
      (node (ref "MAN/EXT") (pin "P$2") (pinfunction "S_P$2") (pintype "passive"))
      (node (ref "R32") (pin "2") (pinfunction "2_2") (pintype "passive"))
    )
    (net (code "5") (name "/V+_SAFE") (class "Default")
      (node (ref "Q1") (pin "1") (pinfunction "C_1") (pintype "passive"))
      (node (ref "U$1") (pin "P$7") (pinfunction "V+_P$7") (pintype "power_in"))
      (node (ref "U$2") (pin "P$7") (pinfunction "V+_P$7") (pintype "power_in"))
      (node (ref "U$3") (pin "P$7") (pinfunction "V+_P$7") (pintype "power_in"))
      (node (ref "U$4") (pin "P$7") (pinfunction "V+_P$7") (pintype "power_in"))
      (node (ref "U$5") (pin "P$7") (pinfunction "V+_P$7") (pintype "power_in"))
      (node (ref "U$6") (pin "P$7") (pinfunction "V+_P$7") (pintype "power_in"))
      (node (ref "U$7") (pin "P$7") (pinfunction "V+_P$7") (pintype "power_in"))
      (node (ref "U$8") (pin "P$7") (pinfunction "V+_P$7") (pintype "power_in"))
    )
    (net (code "6") (name "/V-_SAFE") (class "Default")
      (node (ref "T2") (pin "3") (pinfunction "C_3") (pintype "passive"))
      (node (ref "U$1") (pin "P$6") (pinfunction "V-_P$6") (pintype "power_in"))
      (node (ref "U$2") (pin "P$6") (pinfunction "V-_P$6") (pintype "power_in"))
      (node (ref "U$3") (pin "P$6") (pinfunction "V-_P$6") (pintype "power_in"))
      (node (ref "U$4") (pin "P$6") (pinfunction "V-_P$6") (pintype "power_in"))
      (node (ref "U$5") (pin "P$6") (pinfunction "V-_P$6") (pintype "power_in"))
      (node (ref "U$6") (pin "P$6") (pinfunction "V-_P$6") (pintype "power_in"))
      (node (ref "U$7") (pin "P$6") (pinfunction "V-_P$6") (pintype "power_in"))
      (node (ref "U$8") (pin "P$6") (pinfunction "V-_P$6") (pintype "power_in"))
    )
    (net (code "7") (name "/VIN+1") (class "Default")
      (node (ref "D9") (pin "A") (pinfunction "A_A") (pintype "passive"))
      (node (ref "IC3") (pin "1") (pinfunction "D_1") (pintype "bidirectional"))
      (node (ref "U$4") (pin "P$2") (pinfunction "+IN_P$2") (pintype "input"))
    )
    (net (code "8") (name "/VIN+2") (class "Default")
      (node (ref "D5") (pin "A") (pinfunction "A_A") (pintype "passive"))
      (node (ref "IC4") (pin "1") (pinfunction "D_1") (pintype "bidirectional"))
      (node (ref "U$1") (pin "P$2") (pinfunction "+IN_P$2") (pintype "input"))
    )
    (net (code "9") (name "/VIN+3") (class "Default")
      (node (ref "D13") (pin "A") (pinfunction "A_A") (pintype "passive"))
      (node (ref "IC6") (pin "1") (pinfunction "D_1") (pintype "bidirectional"))
      (node (ref "U$2") (pin "P$2") (pinfunction "+IN_P$2") (pintype "input"))
    )
    (net (code "10") (name "/VIN+4") (class "Default")
      (node (ref "D17") (pin "A") (pinfunction "A_A") (pintype "passive"))
      (node (ref "IC8") (pin "1") (pinfunction "D_1") (pintype "bidirectional"))
      (node (ref "U$3") (pin "P$2") (pinfunction "+IN_P$2") (pintype "input"))
    )
    (net (code "11") (name "/VIN+5") (class "Default")
      (node (ref "D21") (pin "A") (pinfunction "A_A") (pintype "passive"))
      (node (ref "IC10") (pin "1") (pinfunction "D_1") (pintype "bidirectional"))
      (node (ref "U$5") (pin "P$2") (pinfunction "+IN_P$2") (pintype "input"))
    )
    (net (code "12") (name "/VIN+6") (class "Default")
      (node (ref "D25") (pin "A") (pinfunction "A_A") (pintype "passive"))
      (node (ref "IC12") (pin "1") (pinfunction "D_1") (pintype "bidirectional"))
      (node (ref "U$6") (pin "P$2") (pinfunction "+IN_P$2") (pintype "input"))
    )
    (net (code "13") (name "/VIN+7") (class "Default")
      (node (ref "D29") (pin "A") (pinfunction "A_A") (pintype "passive"))
      (node (ref "IC14") (pin "1") (pinfunction "D_1") (pintype "bidirectional"))
      (node (ref "U$7") (pin "P$2") (pinfunction "+IN_P$2") (pintype "input"))
    )
    (net (code "14") (name "/VIN+8") (class "Default")
      (node (ref "D33") (pin "A") (pinfunction "A_A") (pintype "passive"))
      (node (ref "IC16") (pin "1") (pinfunction "D_1") (pintype "bidirectional"))
      (node (ref "U$8") (pin "P$2") (pinfunction "+IN_P$2") (pintype "input"))
    )
    (net (code "15") (name "/VIN-1") (class "Default")
      (node (ref "C7") (pin "1") (pinfunction "1_1") (pintype "passive"))
      (node (ref "D10") (pin "A") (pinfunction "A_A") (pintype "passive"))
      (node (ref "R4") (pin "1") (pinfunction "1_1") (pintype "passive"))
      (node (ref "R5") (pin "2") (pinfunction "2_2") (pintype "passive"))
      (node (ref "U$4") (pin "P$1") (pinfunction "-IN_P$1") (pintype "input"))
    )
    (net (code "16") (name "/VIN-2") (class "Default")
      (node (ref "C11") (pin "1") (pinfunction "1_1") (pintype "passive"))
      (node (ref "D6") (pin "A") (pinfunction "A_A") (pintype "passive"))
      (node (ref "R54") (pin "1") (pinfunction "1_1") (pintype "passive"))
      (node (ref "R57") (pin "2") (pinfunction "2_2") (pintype "passive"))
      (node (ref "U$1") (pin "P$1") (pinfunction "-IN_P$1") (pintype "input"))
    )
    (net (code "17") (name "/VIN-3") (class "Default")
      (node (ref "C13") (pin "1") (pinfunction "1_1") (pintype "passive"))
      (node (ref "D14") (pin "A") (pinfunction "A_A") (pintype "passive"))
      (node (ref "R79") (pin "1") (pinfunction "1_1") (pintype "passive"))
      (node (ref "R82") (pin "2") (pinfunction "2_2") (pintype "passive"))
      (node (ref "U$2") (pin "P$1") (pinfunction "-IN_P$1") (pintype "input"))
    )
    (net (code "18") (name "/VIN-4") (class "Default")
      (node (ref "C15") (pin "1") (pinfunction "1_1") (pintype "passive"))
      (node (ref "D18") (pin "A") (pinfunction "A_A") (pintype "passive"))
      (node (ref "R104") (pin "1") (pinfunction "1_1") (pintype "passive"))
      (node (ref "R107") (pin "2") (pinfunction "2_2") (pintype "passive"))
      (node (ref "U$3") (pin "P$1") (pinfunction "-IN_P$1") (pintype "input"))
    )
    (net (code "19") (name "/VIN-5") (class "Default")
      (node (ref "C17") (pin "1") (pinfunction "1_1") (pintype "passive"))
      (node (ref "D22") (pin "A") (pinfunction "A_A") (pintype "passive"))
      (node (ref "R129") (pin "1") (pinfunction "1_1") (pintype "passive"))
      (node (ref "R132") (pin "2") (pinfunction "2_2") (pintype "passive"))
      (node (ref "U$5") (pin "P$1") (pinfunction "-IN_P$1") (pintype "input"))
    )
    (net (code "20") (name "/VIN-6") (class "Default")
      (node (ref "C19") (pin "1") (pinfunction "1_1") (pintype "passive"))
      (node (ref "D26") (pin "A") (pinfunction "A_A") (pintype "passive"))
      (node (ref "R154") (pin "1") (pinfunction "1_1") (pintype "passive"))
      (node (ref "R157") (pin "2") (pinfunction "2_2") (pintype "passive"))
      (node (ref "U$6") (pin "P$1") (pinfunction "-IN_P$1") (pintype "input"))
    )
    (net (code "21") (name "/VIN-7") (class "Default")
      (node (ref "C21") (pin "1") (pinfunction "1_1") (pintype "passive"))
      (node (ref "D30") (pin "A") (pinfunction "A_A") (pintype "passive"))
      (node (ref "R179") (pin "1") (pinfunction "1_1") (pintype "passive"))
      (node (ref "R182") (pin "2") (pinfunction "2_2") (pintype "passive"))
      (node (ref "U$7") (pin "P$1") (pinfunction "-IN_P$1") (pintype "input"))
    )
    (net (code "22") (name "/VIN-8") (class "Default")
      (node (ref "C23") (pin "1") (pinfunction "1_1") (pintype "passive"))
      (node (ref "D34") (pin "A") (pinfunction "A_A") (pintype "passive"))
      (node (ref "R204") (pin "1") (pinfunction "1_1") (pintype "passive"))
      (node (ref "R207") (pin "2") (pinfunction "2_2") (pintype "passive"))
      (node (ref "U$8") (pin "P$1") (pinfunction "-IN_P$1") (pintype "input"))
    )
    (net (code "23") (name "GND") (class "Default")
      (node (ref "C1") (pin "2") (pinfunction "2_2") (pintype "passive"))
      (node (ref "C2") (pin "2") (pinfunction "2_2") (pintype "passive"))
      (node (ref "C3") (pin "2") (pinfunction "2_2") (pintype "passive"))
      (node (ref "C4") (pin "2") (pinfunction "2_2") (pintype "passive"))
      (node (ref "C6") (pin "2") (pinfunction "2_2") (pintype "passive"))
      (node (ref "D1") (pin "A") (pinfunction "A_A") (pintype "passive"))
      (node (ref "D11") (pin "A") (pinfunction "A_A") (pintype "passive"))
      (node (ref "D15") (pin "A") (pinfunction "A_A") (pintype "passive"))
      (node (ref "D19") (pin "A") (pinfunction "A_A") (pintype "passive"))
      (node (ref "D2") (pin "A") (pinfunction "A_A") (pintype "passive"))
      (node (ref "D23") (pin "A") (pinfunction "A_A") (pintype "passive"))
      (node (ref "D27") (pin "A") (pinfunction "A_A") (pintype "passive"))
      (node (ref "D3") (pin "C") (pinfunction "C_C") (pintype "passive"))
      (node (ref "D31") (pin "A") (pinfunction "A_A") (pintype "passive"))
      (node (ref "D7") (pin "A") (pinfunction "A_A") (pintype "passive"))
      (node (ref "DISPLAY1") (pin "P$2") (pinfunction "S_P$2") (pintype "passive"))
      (node (ref "DISPLAYPOWERJ25") (pin "P$2") (pinfunction "S_P$2") (pintype "passive"))
      (node (ref "EXTERNAL") (pin "10") (pinfunction "F_10") (pintype "passive"))
      (node (ref "EXTERNAL") (pin "12") (pinfunction "F_12") (pintype "passive"))
      (node (ref "EXTERNAL") (pin "14") (pinfunction "F_14") (pintype "passive"))
      (node (ref "EXTERNAL") (pin "16") (pinfunction "F_16") (pintype "passive"))
      (node (ref "EXTERNAL") (pin "2") (pinfunction "F_2") (pintype "passive"))
      (node (ref "EXTERNAL") (pin "25") (pinfunction "F_25") (pintype "passive"))
      (node (ref "EXTERNAL") (pin "4") (pinfunction "F_4") (pintype "passive"))
      (node (ref "EXTERNAL") (pin "6") (pinfunction "F_6") (pintype "passive"))
      (node (ref "EXTERNAL") (pin "8") (pinfunction "F_8") (pintype "passive"))
      (node (ref "HVIN") (pin "P$1") (pinfunction "S_P$1") (pintype "passive"))
      (node (ref "HVIN") (pin "P$2") (pinfunction "S_P$2") (pintype "passive"))
      (node (ref "IC10") (pin "3") (pinfunction "GND_3") (pintype "power_in"))
      (node (ref "IC12") (pin "3") (pinfunction "GND_3") (pintype "power_in"))
      (node (ref "IC14") (pin "3") (pinfunction "GND_3") (pintype "power_in"))
      (node (ref "IC16") (pin "3") (pinfunction "GND_3") (pintype "power_in"))
      (node (ref "IC3") (pin "3") (pinfunction "GND_3") (pintype "power_in"))
      (node (ref "IC4") (pin "3") (pinfunction "GND_3") (pintype "power_in"))
      (node (ref "IC6") (pin "3") (pinfunction "GND_3") (pintype "power_in"))
      (node (ref "IC8") (pin "3") (pinfunction "GND_3") (pintype "power_in"))
      (node (ref "J26") (pin "P$2") (pinfunction "S_P$2") (pintype "passive"))
      (node (ref "POWER") (pin "2") (pinfunction "S_2") (pintype "passive"))
      (node (ref "POWER") (pin "3") (pinfunction "S_3") (pintype "passive"))
      (node (ref "R109") (pin "2") (pinfunction "2_2") (pintype "passive"))
      (node (ref "R122") (pin "1") (pinfunction "1_1") (pintype "passive"))
      (node (ref "R134") (pin "2") (pinfunction "2_2") (pintype "passive"))
      (node (ref "R147") (pin "1") (pinfunction "1_1") (pintype "passive"))
      (node (ref "R15") (pin "2") (pinfunction "2_2") (pintype "passive"))
      (node (ref "R159") (pin "2") (pinfunction "2_2") (pintype "passive"))
      (node (ref "R172") (pin "1") (pinfunction "1_1") (pintype "passive"))
      (node (ref "R184") (pin "2") (pinfunction "2_2") (pintype "passive"))
      (node (ref "R197") (pin "1") (pinfunction "1_1") (pintype "passive"))
      (node (ref "R209") (pin "2") (pinfunction "2_2") (pintype "passive"))
      (node (ref "R26") (pin "1") (pinfunction "1_1") (pintype "passive"))
      (node (ref "R32") (pin "1") (pinfunction "1_1") (pintype "passive"))
      (node (ref "R34") (pin "2") (pinfunction "2_2") (pintype "passive"))
      (node (ref "R47") (pin "1") (pinfunction "1_1") (pintype "passive"))
      (node (ref "R59") (pin "2") (pinfunction "2_2") (pintype "passive"))
      (node (ref "R7") (pin "2") (pinfunction "2_2") (pintype "passive"))
      (node (ref "R72") (pin "1") (pinfunction "1_1") (pintype "passive"))
      (node (ref "R84") (pin "2") (pinfunction "2_2") (pintype "passive"))
      (node (ref "R9") (pin "1") (pinfunction "1_1") (pintype "passive"))
      (node (ref "R97") (pin "1") (pinfunction "1_1") (pintype "passive"))
    )
    (net (code "24") (name "Net-(D1-PadC)") (class "Default")
      (node (ref "D1") (pin "C") (pinfunction "C_C") (pintype "passive"))
      (node (ref "D4") (pin "C") (pinfunction "C_C") (pintype "passive"))
    )
    (net (code "25") (name "Net-(D5-PadC)") (class "Default")
      (node (ref "D5") (pin "C") (pinfunction "C_C") (pintype "passive"))
      (node (ref "D6") (pin "C") (pinfunction "C_C") (pintype "passive"))
    )
    (net (code "26") (name "Net-(D7-PadC)") (class "Default")
      (node (ref "D7") (pin "C") (pinfunction "C_C") (pintype "passive"))
      (node (ref "D8") (pin "C") (pinfunction "C_C") (pintype "passive"))
    )
    (net (code "27") (name "Net-(D10-PadC)") (class "Default")
      (node (ref "D10") (pin "C") (pinfunction "C_C") (pintype "passive"))
      (node (ref "D9") (pin "C") (pinfunction "C_C") (pintype "passive"))
    )
    (net (code "28") (name "Net-(D11-PadC)") (class "Default")
      (node (ref "D11") (pin "C") (pinfunction "C_C") (pintype "passive"))
      (node (ref "D12") (pin "C") (pinfunction "C_C") (pintype "passive"))
    )
    (net (code "29") (name "Net-(D13-PadC)") (class "Default")
      (node (ref "D13") (pin "C") (pinfunction "C_C") (pintype "passive"))
      (node (ref "D14") (pin "C") (pinfunction "C_C") (pintype "passive"))
    )
    (net (code "30") (name "Net-(D15-PadC)") (class "Default")
      (node (ref "D15") (pin "C") (pinfunction "C_C") (pintype "passive"))
      (node (ref "D16") (pin "C") (pinfunction "C_C") (pintype "passive"))
    )
    (net (code "31") (name "Net-(D17-PadC)") (class "Default")
      (node (ref "D17") (pin "C") (pinfunction "C_C") (pintype "passive"))
      (node (ref "D18") (pin "C") (pinfunction "C_C") (pintype "passive"))
    )
    (net (code "32") (name "Net-(D19-PadC)") (class "Default")
      (node (ref "D19") (pin "C") (pinfunction "C_C") (pintype "passive"))
      (node (ref "D20") (pin "C") (pinfunction "C_C") (pintype "passive"))
    )
    (net (code "33") (name "Net-(D21-PadC)") (class "Default")
      (node (ref "D21") (pin "C") (pinfunction "C_C") (pintype "passive"))
      (node (ref "D22") (pin "C") (pinfunction "C_C") (pintype "passive"))
    )
    (net (code "34") (name "Net-(D23-PadC)") (class "Default")
      (node (ref "D23") (pin "C") (pinfunction "C_C") (pintype "passive"))
      (node (ref "D24") (pin "C") (pinfunction "C_C") (pintype "passive"))
    )
    (net (code "35") (name "Net-(D25-PadC)") (class "Default")
      (node (ref "D25") (pin "C") (pinfunction "C_C") (pintype "passive"))
      (node (ref "D26") (pin "C") (pinfunction "C_C") (pintype "passive"))
    )
    (net (code "36") (name "Net-(D27-PadC)") (class "Default")
      (node (ref "D27") (pin "C") (pinfunction "C_C") (pintype "passive"))
      (node (ref "D28") (pin "C") (pinfunction "C_C") (pintype "passive"))
    )
    (net (code "37") (name "Net-(D29-PadC)") (class "Default")
      (node (ref "D29") (pin "C") (pinfunction "C_C") (pintype "passive"))
      (node (ref "D30") (pin "C") (pinfunction "C_C") (pintype "passive"))
    )
    (net (code "38") (name "Net-(D31-PadC)") (class "Default")
      (node (ref "D31") (pin "C") (pinfunction "C_C") (pintype "passive"))
      (node (ref "D32") (pin "C") (pinfunction "C_C") (pintype "passive"))
    )
    (net (code "39") (name "Net-(D33-PadC)") (class "Default")
      (node (ref "D33") (pin "C") (pinfunction "C_C") (pintype "passive"))
      (node (ref "D34") (pin "C") (pinfunction "C_C") (pintype "passive"))
    )
    (net (code "40") (name "Net-(DISPLAY1A-S)") (class "Default")
      (node (ref "DISPLAY1") (pin "P$1") (pinfunction "S_P$1") (pintype "passive"))
      (node (ref "R33") (pin "2") (pinfunction "2_2") (pintype "passive"))
      (node (ref "R34") (pin "1") (pinfunction "1_1") (pintype "passive"))
    )
    (net (code "41") (name "Net-(DISPLAYA-S)") (class "Default")
      (node (ref "DISPLAY") (pin "P$1") (pinfunction "S_P$1") (pintype "passive"))
      (node (ref "R25") (pin "1") (pinfunction "1_1") (pintype "passive"))
      (node (ref "R26") (pin "2") (pinfunction "2_2") (pintype "passive"))
    )
    (net (code "42") (name "Net-(DISPLAYB-S)") (class "Default")
      (node (ref "DISPLAY") (pin "P$2") (pinfunction "S_P$2") (pintype "passive"))
      (node (ref "R46") (pin "1") (pinfunction "1_1") (pintype "passive"))
      (node (ref "R47") (pin "2") (pinfunction "2_2") (pintype "passive"))
    )
    (net (code "43") (name "Net-(DISPLAYC-S)") (class "Default")
      (node (ref "DISPLAY") (pin "P$3") (pinfunction "S_P$3") (pintype "passive"))
      (node (ref "R71") (pin "1") (pinfunction "1_1") (pintype "passive"))
      (node (ref "R72") (pin "2") (pinfunction "2_2") (pintype "passive"))
    )
    (net (code "44") (name "Net-(DISPLAYD-S)") (class "Default")
      (node (ref "DISPLAY") (pin "P$4") (pinfunction "S_P$4") (pintype "passive"))
      (node (ref "R96") (pin "1") (pinfunction "1_1") (pintype "passive"))
      (node (ref "R97") (pin "2") (pinfunction "2_2") (pintype "passive"))
    )
    (net (code "45") (name "Net-(DISPLAYE-S)") (class "Default")
      (node (ref "DISPLAY") (pin "P$5") (pinfunction "S_P$5") (pintype "passive"))
      (node (ref "R121") (pin "1") (pinfunction "1_1") (pintype "passive"))
      (node (ref "R122") (pin "2") (pinfunction "2_2") (pintype "passive"))
    )
    (net (code "46") (name "Net-(DISPLAYF-S)") (class "Default")
      (node (ref "DISPLAY") (pin "P$6") (pinfunction "S_P$6") (pintype "passive"))
      (node (ref "R146") (pin "1") (pinfunction "1_1") (pintype "passive"))
      (node (ref "R147") (pin "2") (pinfunction "2_2") (pintype "passive"))
    )
    (net (code "47") (name "Net-(DISPLAYG-S)") (class "Default")
      (node (ref "DISPLAY") (pin "P$7") (pinfunction "S_P$7") (pintype "passive"))
      (node (ref "R171") (pin "1") (pinfunction "1_1") (pintype "passive"))
      (node (ref "R172") (pin "2") (pinfunction "2_2") (pintype "passive"))
    )
    (net (code "48") (name "Net-(DISPLAYH-S)") (class "Default")
      (node (ref "DISPLAY") (pin "P$8") (pinfunction "S_P$8") (pintype "passive"))
      (node (ref "R196") (pin "1") (pinfunction "1_1") (pintype "passive"))
      (node (ref "R197") (pin "2") (pinfunction "2_2") (pintype "passive"))
    )
    (net (code "49") (name "Net-(EXTERNALA-F)") (class "Default")
      (node (ref "EXTERNAL") (pin "1") (pinfunction "F_1") (pintype "passive"))
      (node (ref "R16") (pin "2") (pinfunction "2_2") (pintype "passive"))
    )
    (net (code "50") (name "Net-(EXTERNALC-F)") (class "Default")
      (node (ref "EXTERNAL") (pin "11") (pinfunction "F_11") (pintype "passive"))
      (node (ref "R137") (pin "2") (pinfunction "2_2") (pintype "passive"))
    )
    (net (code "51") (name "Net-(EXTERNALE-F)") (class "Default")
      (node (ref "EXTERNAL") (pin "13") (pinfunction "F_13") (pintype "passive"))
      (node (ref "R162") (pin "2") (pinfunction "2_2") (pintype "passive"))
    )
    (net (code "52") (name "Net-(EXTERNALG-F)") (class "Default")
      (node (ref "EXTERNAL") (pin "15") (pinfunction "F_15") (pintype "passive"))
      (node (ref "R187") (pin "2") (pinfunction "2_2") (pintype "passive"))
    )
    (net (code "53") (name "Net-(EXTERNALS-F)") (class "Default")
      (node (ref "EXTERNAL") (pin "3") (pinfunction "F_3") (pintype "passive"))
      (node (ref "R37") (pin "2") (pinfunction "2_2") (pintype "passive"))
    )
    (net (code "54") (name "Net-(EXTERNALU-F)") (class "Default")
      (node (ref "EXTERNAL") (pin "5") (pinfunction "F_5") (pintype "passive"))
      (node (ref "R62") (pin "2") (pinfunction "2_2") (pintype "passive"))
    )
    (net (code "55") (name "Net-(EXTERNALW-F)") (class "Default")
      (node (ref "EXTERNAL") (pin "7") (pinfunction "F_7") (pintype "passive"))
      (node (ref "R87") (pin "2") (pinfunction "2_2") (pintype "passive"))
    )
    (net (code "56") (name "Net-(EXTERNALY-F)") (class "Default")
      (node (ref "EXTERNAL") (pin "9") (pinfunction "F_9") (pintype "passive"))
      (node (ref "R112") (pin "2") (pinfunction "2_2") (pintype "passive"))
    )
    (net (code "57") (name "Net-(IC1A-+IN)") (class "Default")
      (node (ref "IC1") (pin "3") (pinfunction "+IN_3") (pintype "input"))
      (node (ref "R39") (pin "1") (pinfunction "1_1") (pintype "passive"))
    )
    (net (code "58") (name "Net-(IC1A--IN)") (class "Default")
      (node (ref "IC1") (pin "2") (pinfunction "-IN_2") (pintype "input"))
      (node (ref "R37") (pin "1") (pinfunction "1_1") (pintype "passive"))
      (node (ref "R38") (pin "2") (pinfunction "2_2") (pintype "passive"))
    )
    (net (code "59") (name "Net-(IC1A-OUT)") (class "Default")
      (node (ref "IC1") (pin "1") (pinfunction "OUT_1") (pintype "output"))
      (node (ref "IC4") (pin "8") (pinfunction "S2_8") (pintype "bidirectional"))
      (node (ref "R38") (pin "1") (pinfunction "1_1") (pintype "passive"))
    )
    (net (code "60") (name "Net-(IC2A-+IN)") (class "Default")
      (node (ref "IC2") (pin "3") (pinfunction "+IN_3") (pintype "input"))
      (node (ref "R18") (pin "1") (pinfunction "1_1") (pintype "passive"))
    )
    (net (code "61") (name "Net-(IC2A--IN)") (class "Default")
      (node (ref "IC2") (pin "2") (pinfunction "-IN_2") (pintype "input"))
      (node (ref "R16") (pin "1") (pinfunction "1_1") (pintype "passive"))
      (node (ref "R17") (pin "2") (pinfunction "2_2") (pintype "passive"))
    )
    (net (code "62") (name "Net-(IC2A-OUT)") (class "Default")
      (node (ref "IC2") (pin "1") (pinfunction "OUT_1") (pintype "output"))
      (node (ref "IC3") (pin "8") (pinfunction "S2_8") (pintype "bidirectional"))
      (node (ref "R17") (pin "1") (pinfunction "1_1") (pintype "passive"))
    )
    (net (code "63") (name "Net-(IC3A-S1)") (class "Default")
      (node (ref "IC3") (pin "2") (pinfunction "S1_2") (pintype "bidirectional"))
      (node (ref "POT1") (pin "P$4") (pinfunction "S_P$4") (pintype "passive"))
    )
    (net (code "64") (name "Net-(IC4A-S1)") (class "Default")
      (node (ref "IC4") (pin "2") (pinfunction "S1_2") (pintype "bidirectional"))
      (node (ref "POT2") (pin "P$4") (pinfunction "S_P$4") (pintype "passive"))
    )
    (net (code "65") (name "Net-(IC5A-+IN)") (class "Default")
      (node (ref "IC5") (pin "3") (pinfunction "+IN_3") (pintype "input"))
      (node (ref "R64") (pin "1") (pinfunction "1_1") (pintype "passive"))
    )
    (net (code "66") (name "Net-(IC5A--IN)") (class "Default")
      (node (ref "IC5") (pin "2") (pinfunction "-IN_2") (pintype "input"))
      (node (ref "R62") (pin "1") (pinfunction "1_1") (pintype "passive"))
      (node (ref "R63") (pin "2") (pinfunction "2_2") (pintype "passive"))
    )
    (net (code "67") (name "Net-(IC5A-OUT)") (class "Default")
      (node (ref "IC5") (pin "1") (pinfunction "OUT_1") (pintype "output"))
      (node (ref "IC6") (pin "8") (pinfunction "S2_8") (pintype "bidirectional"))
      (node (ref "R63") (pin "1") (pinfunction "1_1") (pintype "passive"))
    )
    (net (code "68") (name "Net-(IC6A-S1)") (class "Default")
      (node (ref "IC6") (pin "2") (pinfunction "S1_2") (pintype "bidirectional"))
      (node (ref "POT3") (pin "P$4") (pinfunction "S_P$4") (pintype "passive"))
    )
    (net (code "69") (name "Net-(IC7A-+IN)") (class "Default")
      (node (ref "IC7") (pin "3") (pinfunction "+IN_3") (pintype "input"))
      (node (ref "R89") (pin "1") (pinfunction "1_1") (pintype "passive"))
    )
    (net (code "70") (name "Net-(IC7A--IN)") (class "Default")
      (node (ref "IC7") (pin "2") (pinfunction "-IN_2") (pintype "input"))
      (node (ref "R87") (pin "1") (pinfunction "1_1") (pintype "passive"))
      (node (ref "R88") (pin "2") (pinfunction "2_2") (pintype "passive"))
    )
    (net (code "71") (name "Net-(IC7A-OUT)") (class "Default")
      (node (ref "IC7") (pin "1") (pinfunction "OUT_1") (pintype "output"))
      (node (ref "IC8") (pin "8") (pinfunction "S2_8") (pintype "bidirectional"))
      (node (ref "R88") (pin "1") (pinfunction "1_1") (pintype "passive"))
    )
    (net (code "72") (name "Net-(IC8A-S1)") (class "Default")
      (node (ref "IC8") (pin "2") (pinfunction "S1_2") (pintype "bidirectional"))
      (node (ref "POT4") (pin "P$4") (pinfunction "S_P$4") (pintype "passive"))
    )
    (net (code "73") (name "Net-(IC9A-+IN)") (class "Default")
      (node (ref "IC9") (pin "3") (pinfunction "+IN_3") (pintype "input"))
      (node (ref "R114") (pin "1") (pinfunction "1_1") (pintype "passive"))
    )
    (net (code "74") (name "Net-(IC9A--IN)") (class "Default")
      (node (ref "IC9") (pin "2") (pinfunction "-IN_2") (pintype "input"))
      (node (ref "R112") (pin "1") (pinfunction "1_1") (pintype "passive"))
      (node (ref "R113") (pin "2") (pinfunction "2_2") (pintype "passive"))
    )
    (net (code "75") (name "Net-(IC10A-S1)") (class "Default")
      (node (ref "IC10") (pin "2") (pinfunction "S1_2") (pintype "bidirectional"))
      (node (ref "POT5") (pin "P$4") (pinfunction "S_P$4") (pintype "passive"))
    )
    (net (code "76") (name "Net-(IC10A-S2)") (class "Default")
      (node (ref "IC10") (pin "8") (pinfunction "S2_8") (pintype "bidirectional"))
      (node (ref "IC9") (pin "1") (pinfunction "OUT_1") (pintype "output"))
      (node (ref "R113") (pin "1") (pinfunction "1_1") (pintype "passive"))
    )
    (net (code "77") (name "Net-(IC11A-+IN)") (class "Default")
      (node (ref "IC11") (pin "3") (pinfunction "+IN_3") (pintype "input"))
      (node (ref "R139") (pin "1") (pinfunction "1_1") (pintype "passive"))
    )
    (net (code "78") (name "Net-(IC11A--IN)") (class "Default")
      (node (ref "IC11") (pin "2") (pinfunction "-IN_2") (pintype "input"))
      (node (ref "R137") (pin "1") (pinfunction "1_1") (pintype "passive"))
      (node (ref "R138") (pin "2") (pinfunction "2_2") (pintype "passive"))
    )
    (net (code "79") (name "Net-(IC11A-OUT)") (class "Default")
      (node (ref "IC11") (pin "1") (pinfunction "OUT_1") (pintype "output"))
      (node (ref "IC12") (pin "8") (pinfunction "S2_8") (pintype "bidirectional"))
      (node (ref "R138") (pin "1") (pinfunction "1_1") (pintype "passive"))
    )
    (net (code "80") (name "Net-(IC12A-S1)") (class "Default")
      (node (ref "IC12") (pin "2") (pinfunction "S1_2") (pintype "bidirectional"))
      (node (ref "POT6") (pin "P$4") (pinfunction "S_P$4") (pintype "passive"))
    )
    (net (code "81") (name "Net-(IC13A-+IN)") (class "Default")
      (node (ref "IC13") (pin "3") (pinfunction "+IN_3") (pintype "input"))
      (node (ref "R164") (pin "1") (pinfunction "1_1") (pintype "passive"))
    )
    (net (code "82") (name "Net-(IC13A--IN)") (class "Default")
      (node (ref "IC13") (pin "2") (pinfunction "-IN_2") (pintype "input"))
      (node (ref "R162") (pin "1") (pinfunction "1_1") (pintype "passive"))
      (node (ref "R163") (pin "2") (pinfunction "2_2") (pintype "passive"))
    )
    (net (code "83") (name "Net-(IC13A-OUT)") (class "Default")
      (node (ref "IC13") (pin "1") (pinfunction "OUT_1") (pintype "output"))
      (node (ref "IC14") (pin "8") (pinfunction "S2_8") (pintype "bidirectional"))
      (node (ref "R163") (pin "1") (pinfunction "1_1") (pintype "passive"))
    )
    (net (code "84") (name "Net-(IC14A-S1)") (class "Default")
      (node (ref "IC14") (pin "2") (pinfunction "S1_2") (pintype "bidirectional"))
      (node (ref "POT7") (pin "P$4") (pinfunction "S_P$4") (pintype "passive"))
    )
    (net (code "85") (name "Net-(IC15A-+IN)") (class "Default")
      (node (ref "IC15") (pin "3") (pinfunction "+IN_3") (pintype "input"))
      (node (ref "R189") (pin "1") (pinfunction "1_1") (pintype "passive"))
    )
    (net (code "86") (name "Net-(IC15A--IN)") (class "Default")
      (node (ref "IC15") (pin "2") (pinfunction "-IN_2") (pintype "input"))
      (node (ref "R187") (pin "1") (pinfunction "1_1") (pintype "passive"))
      (node (ref "R188") (pin "2") (pinfunction "2_2") (pintype "passive"))
    )
    (net (code "87") (name "Net-(IC15A-OUT)") (class "Default")
      (node (ref "IC15") (pin "1") (pinfunction "OUT_1") (pintype "output"))
      (node (ref "IC16") (pin "8") (pinfunction "S2_8") (pintype "bidirectional"))
      (node (ref "R188") (pin "1") (pinfunction "1_1") (pintype "passive"))
    )
    (net (code "88") (name "Net-(IC16A-S1)") (class "Default")
      (node (ref "IC16") (pin "2") (pinfunction "S1_2") (pintype "bidirectional"))
      (node (ref "POT8") (pin "P$4") (pinfunction "S_P$4") (pintype "passive"))
    )
    (net (code "89") (name "Net-(J23A-S)") (class "Default")
      (node (ref "J23") (pin "P$1") (pinfunction "S_P$1") (pintype "passive"))
      (node (ref "R33") (pin "1") (pinfunction "1_1") (pintype "passive"))
    )
    (net (code "90") (name "Net-(J26A-S)") (class "Default")
      (node (ref "J26") (pin "P$1") (pinfunction "S_P$1") (pintype "passive"))
      (node (ref "R35") (pin "1") (pinfunction "1_1") (pintype "passive"))
    )
    (net (code "91") (name "Net-(OUTB-P$1)") (class "Default")
      (node (ref "C11") (pin "2") (pinfunction "2_2") (pintype "passive"))
      (node (ref "D4") (pin "A") (pinfunction "A_A") (pintype "passive"))
      (node (ref "OUT") (pin "P$2") (pinfunction "P$1_P$2") (pintype "bidirectional"))
      (node (ref "R42") (pin "2") (pinfunction "2_2") (pintype "passive"))
      (node (ref "R56") (pin "2") (pinfunction "2_2") (pintype "passive"))
      (node (ref "U$1") (pin "P$5") (pinfunction "OUT_P$5") (pintype "output"))
    )
    (net (code "92") (name "Net-(OUTC-P$1)") (class "Default")
      (node (ref "C13") (pin "2") (pinfunction "2_2") (pintype "passive"))
      (node (ref "D12") (pin "A") (pinfunction "A_A") (pintype "passive"))
      (node (ref "OUT") (pin "P$3") (pinfunction "P$1_P$3") (pintype "bidirectional"))
      (node (ref "R67") (pin "2") (pinfunction "2_2") (pintype "passive"))
      (node (ref "R81") (pin "2") (pinfunction "2_2") (pintype "passive"))
      (node (ref "U$2") (pin "P$5") (pinfunction "OUT_P$5") (pintype "output"))
    )
    (net (code "93") (name "Net-(OUTD-P$1)") (class "Default")
      (node (ref "C15") (pin "2") (pinfunction "2_2") (pintype "passive"))
      (node (ref "D16") (pin "A") (pinfunction "A_A") (pintype "passive"))
      (node (ref "OUT") (pin "P$4") (pinfunction "P$1_P$4") (pintype "bidirectional"))
      (node (ref "R106") (pin "2") (pinfunction "2_2") (pintype "passive"))
      (node (ref "R92") (pin "2") (pinfunction "2_2") (pintype "passive"))
      (node (ref "U$3") (pin "P$5") (pinfunction "OUT_P$5") (pintype "output"))
    )
    (net (code "94") (name "Net-(OUTE-P$1)") (class "Default")
      (node (ref "C17") (pin "2") (pinfunction "2_2") (pintype "passive"))
      (node (ref "D20") (pin "A") (pinfunction "A_A") (pintype "passive"))
      (node (ref "OUT") (pin "P$5") (pinfunction "P$1_P$5") (pintype "bidirectional"))
      (node (ref "R117") (pin "2") (pinfunction "2_2") (pintype "passive"))
      (node (ref "R131") (pin "2") (pinfunction "2_2") (pintype "passive"))
      (node (ref "U$5") (pin "P$5") (pinfunction "OUT_P$5") (pintype "output"))
    )
    (net (code "95") (name "Net-(OUTF-P$1)") (class "Default")
      (node (ref "C19") (pin "2") (pinfunction "2_2") (pintype "passive"))
      (node (ref "D24") (pin "A") (pinfunction "A_A") (pintype "passive"))
      (node (ref "OUT") (pin "P$6") (pinfunction "P$1_P$6") (pintype "bidirectional"))
      (node (ref "R142") (pin "2") (pinfunction "2_2") (pintype "passive"))
      (node (ref "R156") (pin "2") (pinfunction "2_2") (pintype "passive"))
      (node (ref "U$6") (pin "P$5") (pinfunction "OUT_P$5") (pintype "output"))
    )
    (net (code "96") (name "Net-(OUTG-P$1)") (class "Default")
      (node (ref "C21") (pin "2") (pinfunction "2_2") (pintype "passive"))
      (node (ref "D28") (pin "A") (pinfunction "A_A") (pintype "passive"))
      (node (ref "OUT") (pin "P$7") (pinfunction "P$1_P$7") (pintype "bidirectional"))
      (node (ref "R167") (pin "2") (pinfunction "2_2") (pintype "passive"))
      (node (ref "R181") (pin "2") (pinfunction "2_2") (pintype "passive"))
      (node (ref "U$7") (pin "P$5") (pinfunction "OUT_P$5") (pintype "output"))
    )
    (net (code "97") (name "Net-(OUTH-P$1)") (class "Default")
      (node (ref "C23") (pin "2") (pinfunction "2_2") (pintype "passive"))
      (node (ref "D32") (pin "A") (pinfunction "A_A") (pintype "passive"))
      (node (ref "OUT") (pin "P$8") (pinfunction "P$1_P$8") (pintype "bidirectional"))
      (node (ref "R192") (pin "2") (pinfunction "2_2") (pintype "passive"))
      (node (ref "R206") (pin "2") (pinfunction "2_2") (pintype "passive"))
      (node (ref "U$8") (pin "P$5") (pinfunction "OUT_P$5") (pintype "output"))
    )
    (net (code "98") (name "Net-(POT1A-S)") (class "Default")
      (node (ref "POT1") (pin "P$1") (pinfunction "S_P$1") (pintype "passive"))
      (node (ref "R14") (pin "2") (pinfunction "2_2") (pintype "passive"))
    )
    (net (code "99") (name "Net-(POT1B-S)") (class "Default")
      (node (ref "POT1") (pin "P$2") (pinfunction "S_P$2") (pintype "passive"))
      (node (ref "R13") (pin "2") (pinfunction "2_2") (pintype "passive"))
    )
    (net (code "100") (name "Net-(POT2A-S)") (class "Default")
      (node (ref "POT2") (pin "P$1") (pinfunction "S_P$1") (pintype "passive"))
      (node (ref "R36") (pin "2") (pinfunction "2_2") (pintype "passive"))
    )
    (net (code "101") (name "Net-(POT2B-S)") (class "Default")
      (node (ref "POT2") (pin "P$2") (pinfunction "S_P$2") (pintype "passive"))
      (node (ref "R1") (pin "2") (pinfunction "2_2") (pintype "passive"))
    )
    (net (code "102") (name "Net-(POT3A-S)") (class "Default")
      (node (ref "POT3") (pin "P$1") (pinfunction "S_P$1") (pintype "passive"))
      (node (ref "R61") (pin "2") (pinfunction "2_2") (pintype "passive"))
    )
    (net (code "103") (name "Net-(POT3B-S)") (class "Default")
      (node (ref "POT3") (pin "P$2") (pinfunction "S_P$2") (pintype "passive"))
      (node (ref "R60") (pin "2") (pinfunction "2_2") (pintype "passive"))
    )
    (net (code "104") (name "Net-(POT4A-S)") (class "Default")
      (node (ref "POT4") (pin "P$1") (pinfunction "S_P$1") (pintype "passive"))
      (node (ref "R86") (pin "2") (pinfunction "2_2") (pintype "passive"))
    )
    (net (code "105") (name "Net-(POT4B-S)") (class "Default")
      (node (ref "POT4") (pin "P$2") (pinfunction "S_P$2") (pintype "passive"))
      (node (ref "R85") (pin "2") (pinfunction "2_2") (pintype "passive"))
    )
    (net (code "106") (name "Net-(POT5A-S)") (class "Default")
      (node (ref "POT5") (pin "P$1") (pinfunction "S_P$1") (pintype "passive"))
      (node (ref "R111") (pin "2") (pinfunction "2_2") (pintype "passive"))
    )
    (net (code "107") (name "Net-(POT5B-S)") (class "Default")
      (node (ref "POT5") (pin "P$2") (pinfunction "S_P$2") (pintype "passive"))
      (node (ref "R110") (pin "2") (pinfunction "2_2") (pintype "passive"))
    )
    (net (code "108") (name "Net-(POT6A-S)") (class "Default")
      (node (ref "POT6") (pin "P$1") (pinfunction "S_P$1") (pintype "passive"))
      (node (ref "R136") (pin "2") (pinfunction "2_2") (pintype "passive"))
    )
    (net (code "109") (name "Net-(POT6B-S)") (class "Default")
      (node (ref "POT6") (pin "P$2") (pinfunction "S_P$2") (pintype "passive"))
      (node (ref "R135") (pin "2") (pinfunction "2_2") (pintype "passive"))
    )
    (net (code "110") (name "Net-(POT7A-S)") (class "Default")
      (node (ref "POT7") (pin "P$1") (pinfunction "S_P$1") (pintype "passive"))
      (node (ref "R161") (pin "2") (pinfunction "2_2") (pintype "passive"))
    )
    (net (code "111") (name "Net-(POT7B-S)") (class "Default")
      (node (ref "POT7") (pin "P$2") (pinfunction "S_P$2") (pintype "passive"))
      (node (ref "R160") (pin "2") (pinfunction "2_2") (pintype "passive"))
    )
    (net (code "112") (name "Net-(POT8A-S)") (class "Default")
      (node (ref "POT8") (pin "P$1") (pinfunction "S_P$1") (pintype "passive"))
      (node (ref "R186") (pin "2") (pinfunction "2_2") (pintype "passive"))
    )
    (net (code "113") (name "Net-(POT8B-S)") (class "Default")
      (node (ref "POT8") (pin "P$2") (pinfunction "S_P$2") (pintype "passive"))
      (node (ref "R185") (pin "2") (pinfunction "2_2") (pintype "passive"))
    )
    (net (code "114") (name "Net-(Q1-B)") (class "Default")
      (node (ref "C8") (pin "2") (pinfunction "2_2") (pintype "passive"))
      (node (ref "Q1") (pin "2") (pinfunction "B_2") (pintype "passive"))
      (node (ref "Q2") (pin "1") (pinfunction "C_1") (pintype "passive"))
      (node (ref "R9") (pin "2") (pinfunction "2_2") (pintype "passive"))
    )
    (net (code "115") (name "Net-(Q1-E)") (class "Default")
      (node (ref "Q1") (pin "3") (pinfunction "E_3") (pintype "passive"))
      (node (ref "R10") (pin "2") (pinfunction "2_2") (pintype "passive"))
      (node (ref "R11") (pin "2") (pinfunction "2_2") (pintype "passive"))
    )
    (net (code "116") (name "Net-(Q2-B)") (class "Default")
      (node (ref "C8") (pin "1") (pinfunction "1_1") (pintype "passive"))
      (node (ref "Q2") (pin "2") (pinfunction "B_2") (pintype "passive"))
      (node (ref "R10") (pin "1") (pinfunction "1_1") (pintype "passive"))
    )
    (net (code "117") (name "Net-(R2-Pad1)") (class "Default")
      (node (ref "R2") (pin "1") (pinfunction "1_1") (pintype "passive"))
      (node (ref "R4") (pin "2") (pinfunction "2_2") (pintype "passive"))
    )
    (net (code "118") (name "Net-(R2-Pad2)") (class "Default")
      (node (ref "R2") (pin "2") (pinfunction "2_2") (pintype "passive"))
      (node (ref "R3") (pin "1") (pinfunction "1_1") (pintype "passive"))
    )
    (net (code "119") (name "Net-(R5-Pad1)") (class "Default")
      (node (ref "R5") (pin "1") (pinfunction "1_1") (pintype "passive"))
      (node (ref "R6") (pin "2") (pinfunction "2_2") (pintype "passive"))
    )
    (net (code "120") (name "Net-(R6-Pad1)") (class "Default")
      (node (ref "R6") (pin "1") (pinfunction "1_1") (pintype "passive"))
      (node (ref "R7") (pin "1") (pinfunction "1_1") (pintype "passive"))
    )
    (net (code "121") (name "Net-(R11-Pad1)") (class "Default")
      (node (ref "R11") (pin "1") (pinfunction "1_1") (pintype "passive"))
      (node (ref "R27") (pin "2") (pinfunction "2_2") (pintype "passive"))
    )
    (net (code "122") (name "Net-(R18-Pad2)") (class "Default")
      (node (ref "R18") (pin "2") (pinfunction "2_2") (pintype "passive"))
      (node (ref "R19") (pin "2") (pinfunction "2_2") (pintype "passive"))
      (node (ref "R20") (pin "1") (pinfunction "1_1") (pintype "passive"))
    )
    (net (code "123") (name "Net-(R21-Pad1)") (class "Default")
      (node (ref "R21") (pin "1") (pinfunction "1_1") (pintype "passive"))
      (node (ref "R22") (pin "2") (pinfunction "2_2") (pintype "passive"))
    )
    (net (code "124") (name "Net-(R22-Pad1)") (class "Default")
      (node (ref "R22") (pin "1") (pinfunction "1_1") (pintype "passive"))
      (node (ref "R23") (pin "2") (pinfunction "2_2") (pintype "passive"))
    )
    (net (code "125") (name "Net-(R23-Pad1)") (class "Default")
      (node (ref "R23") (pin "1") (pinfunction "1_1") (pintype "passive"))
      (node (ref "R24") (pin "2") (pinfunction "2_2") (pintype "passive"))
    )
    (net (code "126") (name "Net-(R24-Pad1)") (class "Default")
      (node (ref "R24") (pin "1") (pinfunction "1_1") (pintype "passive"))
      (node (ref "R25") (pin "2") (pinfunction "2_2") (pintype "passive"))
    )
    (net (code "127") (name "Net-(R27-Pad1)") (class "Default")
      (node (ref "R27") (pin "1") (pinfunction "1_1") (pintype "passive"))
      (node (ref "R8") (pin "2") (pinfunction "2_2") (pintype "passive"))
    )
    (net (code "128") (name "Net-(R28-Pad2)") (class "Default")
      (node (ref "R28") (pin "2") (pinfunction "2_2") (pintype "passive"))
      (node (ref "R29") (pin "1") (pinfunction "1_1") (pintype "passive"))
    )
    (net (code "129") (name "Net-(R29-Pad2)") (class "Default")
      (node (ref "R29") (pin "2") (pinfunction "2_2") (pintype "passive"))
      (node (ref "R30") (pin "1") (pinfunction "1_1") (pintype "passive"))
    )
    (net (code "130") (name "Net-(R39-Pad2)") (class "Default")
      (node (ref "R39") (pin "2") (pinfunction "2_2") (pintype "passive"))
      (node (ref "R40") (pin "2") (pinfunction "2_2") (pintype "passive"))
      (node (ref "R41") (pin "1") (pinfunction "1_1") (pintype "passive"))
    )
    (net (code "131") (name "Net-(R42-Pad1)") (class "Default")
      (node (ref "R42") (pin "1") (pinfunction "1_1") (pintype "passive"))
      (node (ref "R43") (pin "2") (pinfunction "2_2") (pintype "passive"))
    )
    (net (code "132") (name "Net-(R43-Pad1)") (class "Default")
      (node (ref "R43") (pin "1") (pinfunction "1_1") (pintype "passive"))
      (node (ref "R44") (pin "2") (pinfunction "2_2") (pintype "passive"))
    )
    (net (code "133") (name "Net-(R44-Pad1)") (class "Default")
      (node (ref "R44") (pin "1") (pinfunction "1_1") (pintype "passive"))
      (node (ref "R45") (pin "2") (pinfunction "2_2") (pintype "passive"))
    )
    (net (code "134") (name "Net-(R45-Pad1)") (class "Default")
      (node (ref "R45") (pin "1") (pinfunction "1_1") (pintype "passive"))
      (node (ref "R46") (pin "2") (pinfunction "2_2") (pintype "passive"))
    )
    (net (code "135") (name "Net-(R54-Pad2)") (class "Default")
      (node (ref "R54") (pin "2") (pinfunction "2_2") (pintype "passive"))
      (node (ref "R55") (pin "1") (pinfunction "1_1") (pintype "passive"))
    )
    (net (code "136") (name "Net-(R55-Pad2)") (class "Default")
      (node (ref "R55") (pin "2") (pinfunction "2_2") (pintype "passive"))
      (node (ref "R56") (pin "1") (pinfunction "1_1") (pintype "passive"))
    )
    (net (code "137") (name "Net-(R57-Pad1)") (class "Default")
      (node (ref "R57") (pin "1") (pinfunction "1_1") (pintype "passive"))
      (node (ref "R58") (pin "2") (pinfunction "2_2") (pintype "passive"))
    )
    (net (code "138") (name "Net-(R58-Pad1)") (class "Default")
      (node (ref "R58") (pin "1") (pinfunction "1_1") (pintype "passive"))
      (node (ref "R59") (pin "1") (pinfunction "1_1") (pintype "passive"))
    )
    (net (code "139") (name "Net-(R64-Pad2)") (class "Default")
      (node (ref "R64") (pin "2") (pinfunction "2_2") (pintype "passive"))
      (node (ref "R65") (pin "2") (pinfunction "2_2") (pintype "passive"))
      (node (ref "R66") (pin "1") (pinfunction "1_1") (pintype "passive"))
    )
    (net (code "140") (name "Net-(R67-Pad1)") (class "Default")
      (node (ref "R67") (pin "1") (pinfunction "1_1") (pintype "passive"))
      (node (ref "R68") (pin "2") (pinfunction "2_2") (pintype "passive"))
    )
    (net (code "141") (name "Net-(R68-Pad1)") (class "Default")
      (node (ref "R68") (pin "1") (pinfunction "1_1") (pintype "passive"))
      (node (ref "R69") (pin "2") (pinfunction "2_2") (pintype "passive"))
    )
    (net (code "142") (name "Net-(R69-Pad1)") (class "Default")
      (node (ref "R69") (pin "1") (pinfunction "1_1") (pintype "passive"))
      (node (ref "R70") (pin "2") (pinfunction "2_2") (pintype "passive"))
    )
    (net (code "143") (name "Net-(R70-Pad1)") (class "Default")
      (node (ref "R70") (pin "1") (pinfunction "1_1") (pintype "passive"))
      (node (ref "R71") (pin "2") (pinfunction "2_2") (pintype "passive"))
    )
    (net (code "144") (name "Net-(R79-Pad2)") (class "Default")
      (node (ref "R79") (pin "2") (pinfunction "2_2") (pintype "passive"))
      (node (ref "R80") (pin "1") (pinfunction "1_1") (pintype "passive"))
    )
    (net (code "145") (name "Net-(R80-Pad2)") (class "Default")
      (node (ref "R80") (pin "2") (pinfunction "2_2") (pintype "passive"))
      (node (ref "R81") (pin "1") (pinfunction "1_1") (pintype "passive"))
    )
    (net (code "146") (name "Net-(R82-Pad1)") (class "Default")
      (node (ref "R82") (pin "1") (pinfunction "1_1") (pintype "passive"))
      (node (ref "R83") (pin "2") (pinfunction "2_2") (pintype "passive"))
    )
    (net (code "147") (name "Net-(R83-Pad1)") (class "Default")
      (node (ref "R83") (pin "1") (pinfunction "1_1") (pintype "passive"))
      (node (ref "R84") (pin "1") (pinfunction "1_1") (pintype "passive"))
    )
    (net (code "148") (name "Net-(R89-Pad2)") (class "Default")
      (node (ref "R89") (pin "2") (pinfunction "2_2") (pintype "passive"))
      (node (ref "R90") (pin "2") (pinfunction "2_2") (pintype "passive"))
      (node (ref "R91") (pin "1") (pinfunction "1_1") (pintype "passive"))
    )
    (net (code "149") (name "Net-(R92-Pad1)") (class "Default")
      (node (ref "R92") (pin "1") (pinfunction "1_1") (pintype "passive"))
      (node (ref "R93") (pin "2") (pinfunction "2_2") (pintype "passive"))
    )
    (net (code "150") (name "Net-(R93-Pad1)") (class "Default")
      (node (ref "R93") (pin "1") (pinfunction "1_1") (pintype "passive"))
      (node (ref "R94") (pin "2") (pinfunction "2_2") (pintype "passive"))
    )
    (net (code "151") (name "Net-(R94-Pad1)") (class "Default")
      (node (ref "R94") (pin "1") (pinfunction "1_1") (pintype "passive"))
      (node (ref "R95") (pin "2") (pinfunction "2_2") (pintype "passive"))
    )
    (net (code "152") (name "Net-(R95-Pad1)") (class "Default")
      (node (ref "R95") (pin "1") (pinfunction "1_1") (pintype "passive"))
      (node (ref "R96") (pin "2") (pinfunction "2_2") (pintype "passive"))
    )
    (net (code "153") (name "Net-(R104-Pad2)") (class "Default")
      (node (ref "R104") (pin "2") (pinfunction "2_2") (pintype "passive"))
      (node (ref "R105") (pin "1") (pinfunction "1_1") (pintype "passive"))
    )
    (net (code "154") (name "Net-(R105-Pad2)") (class "Default")
      (node (ref "R105") (pin "2") (pinfunction "2_2") (pintype "passive"))
      (node (ref "R106") (pin "1") (pinfunction "1_1") (pintype "passive"))
    )
    (net (code "155") (name "Net-(R107-Pad1)") (class "Default")
      (node (ref "R107") (pin "1") (pinfunction "1_1") (pintype "passive"))
      (node (ref "R108") (pin "2") (pinfunction "2_2") (pintype "passive"))
    )
    (net (code "156") (name "Net-(R108-Pad1)") (class "Default")
      (node (ref "R108") (pin "1") (pinfunction "1_1") (pintype "passive"))
      (node (ref "R109") (pin "1") (pinfunction "1_1") (pintype "passive"))
    )
    (net (code "157") (name "Net-(R114-Pad2)") (class "Default")
      (node (ref "R114") (pin "2") (pinfunction "2_2") (pintype "passive"))
      (node (ref "R115") (pin "2") (pinfunction "2_2") (pintype "passive"))
      (node (ref "R116") (pin "1") (pinfunction "1_1") (pintype "passive"))
    )
    (net (code "158") (name "Net-(R117-Pad1)") (class "Default")
      (node (ref "R117") (pin "1") (pinfunction "1_1") (pintype "passive"))
      (node (ref "R118") (pin "2") (pinfunction "2_2") (pintype "passive"))
    )
    (net (code "159") (name "Net-(R118-Pad1)") (class "Default")
      (node (ref "R118") (pin "1") (pinfunction "1_1") (pintype "passive"))
      (node (ref "R119") (pin "2") (pinfunction "2_2") (pintype "passive"))
    )
    (net (code "160") (name "Net-(R119-Pad1)") (class "Default")
      (node (ref "R119") (pin "1") (pinfunction "1_1") (pintype "passive"))
      (node (ref "R120") (pin "2") (pinfunction "2_2") (pintype "passive"))
    )
    (net (code "161") (name "Net-(R120-Pad1)") (class "Default")
      (node (ref "R120") (pin "1") (pinfunction "1_1") (pintype "passive"))
      (node (ref "R121") (pin "2") (pinfunction "2_2") (pintype "passive"))
    )
    (net (code "162") (name "Net-(R129-Pad2)") (class "Default")
      (node (ref "R129") (pin "2") (pinfunction "2_2") (pintype "passive"))
      (node (ref "R130") (pin "1") (pinfunction "1_1") (pintype "passive"))
    )
    (net (code "163") (name "Net-(R130-Pad2)") (class "Default")
      (node (ref "R130") (pin "2") (pinfunction "2_2") (pintype "passive"))
      (node (ref "R131") (pin "1") (pinfunction "1_1") (pintype "passive"))
    )
    (net (code "164") (name "Net-(R132-Pad1)") (class "Default")
      (node (ref "R132") (pin "1") (pinfunction "1_1") (pintype "passive"))
      (node (ref "R133") (pin "2") (pinfunction "2_2") (pintype "passive"))
    )
    (net (code "165") (name "Net-(R133-Pad1)") (class "Default")
      (node (ref "R133") (pin "1") (pinfunction "1_1") (pintype "passive"))
      (node (ref "R134") (pin "1") (pinfunction "1_1") (pintype "passive"))
    )
    (net (code "166") (name "Net-(R139-Pad2)") (class "Default")
      (node (ref "R139") (pin "2") (pinfunction "2_2") (pintype "passive"))
      (node (ref "R140") (pin "2") (pinfunction "2_2") (pintype "passive"))
      (node (ref "R141") (pin "1") (pinfunction "1_1") (pintype "passive"))
    )
    (net (code "167") (name "Net-(R142-Pad1)") (class "Default")
      (node (ref "R142") (pin "1") (pinfunction "1_1") (pintype "passive"))
      (node (ref "R143") (pin "2") (pinfunction "2_2") (pintype "passive"))
    )
    (net (code "168") (name "Net-(R143-Pad1)") (class "Default")
      (node (ref "R143") (pin "1") (pinfunction "1_1") (pintype "passive"))
      (node (ref "R144") (pin "2") (pinfunction "2_2") (pintype "passive"))
    )
    (net (code "169") (name "Net-(R144-Pad1)") (class "Default")
      (node (ref "R144") (pin "1") (pinfunction "1_1") (pintype "passive"))
      (node (ref "R145") (pin "2") (pinfunction "2_2") (pintype "passive"))
    )
    (net (code "170") (name "Net-(R145-Pad1)") (class "Default")
      (node (ref "R145") (pin "1") (pinfunction "1_1") (pintype "passive"))
      (node (ref "R146") (pin "2") (pinfunction "2_2") (pintype "passive"))
    )
    (net (code "171") (name "Net-(R154-Pad2)") (class "Default")
      (node (ref "R154") (pin "2") (pinfunction "2_2") (pintype "passive"))
      (node (ref "R155") (pin "1") (pinfunction "1_1") (pintype "passive"))
    )
    (net (code "172") (name "Net-(R155-Pad2)") (class "Default")
      (node (ref "R155") (pin "2") (pinfunction "2_2") (pintype "passive"))
      (node (ref "R156") (pin "1") (pinfunction "1_1") (pintype "passive"))
    )
    (net (code "173") (name "Net-(R157-Pad1)") (class "Default")
      (node (ref "R157") (pin "1") (pinfunction "1_1") (pintype "passive"))
      (node (ref "R158") (pin "2") (pinfunction "2_2") (pintype "passive"))
    )
    (net (code "174") (name "Net-(R158-Pad1)") (class "Default")
      (node (ref "R158") (pin "1") (pinfunction "1_1") (pintype "passive"))
      (node (ref "R159") (pin "1") (pinfunction "1_1") (pintype "passive"))
    )
    (net (code "175") (name "Net-(R164-Pad2)") (class "Default")
      (node (ref "R164") (pin "2") (pinfunction "2_2") (pintype "passive"))
      (node (ref "R165") (pin "2") (pinfunction "2_2") (pintype "passive"))
      (node (ref "R166") (pin "1") (pinfunction "1_1") (pintype "passive"))
    )
    (net (code "176") (name "Net-(R167-Pad1)") (class "Default")
      (node (ref "R167") (pin "1") (pinfunction "1_1") (pintype "passive"))
      (node (ref "R168") (pin "2") (pinfunction "2_2") (pintype "passive"))
    )
    (net (code "177") (name "Net-(R168-Pad1)") (class "Default")
      (node (ref "R168") (pin "1") (pinfunction "1_1") (pintype "passive"))
      (node (ref "R169") (pin "2") (pinfunction "2_2") (pintype "passive"))
    )
    (net (code "178") (name "Net-(R169-Pad1)") (class "Default")
      (node (ref "R169") (pin "1") (pinfunction "1_1") (pintype "passive"))
      (node (ref "R170") (pin "2") (pinfunction "2_2") (pintype "passive"))
    )
    (net (code "179") (name "Net-(R170-Pad1)") (class "Default")
      (node (ref "R170") (pin "1") (pinfunction "1_1") (pintype "passive"))
      (node (ref "R171") (pin "2") (pinfunction "2_2") (pintype "passive"))
    )
    (net (code "180") (name "Net-(R179-Pad2)") (class "Default")
      (node (ref "R179") (pin "2") (pinfunction "2_2") (pintype "passive"))
      (node (ref "R180") (pin "1") (pinfunction "1_1") (pintype "passive"))
    )
    (net (code "181") (name "Net-(R180-Pad2)") (class "Default")
      (node (ref "R180") (pin "2") (pinfunction "2_2") (pintype "passive"))
      (node (ref "R181") (pin "1") (pinfunction "1_1") (pintype "passive"))
    )
    (net (code "182") (name "Net-(R182-Pad1)") (class "Default")
      (node (ref "R182") (pin "1") (pinfunction "1_1") (pintype "passive"))
      (node (ref "R183") (pin "2") (pinfunction "2_2") (pintype "passive"))
    )
    (net (code "183") (name "Net-(R183-Pad1)") (class "Default")
      (node (ref "R183") (pin "1") (pinfunction "1_1") (pintype "passive"))
      (node (ref "R184") (pin "1") (pinfunction "1_1") (pintype "passive"))
    )
    (net (code "184") (name "Net-(R189-Pad2)") (class "Default")
      (node (ref "R189") (pin "2") (pinfunction "2_2") (pintype "passive"))
      (node (ref "R190") (pin "2") (pinfunction "2_2") (pintype "passive"))
      (node (ref "R191") (pin "1") (pinfunction "1_1") (pintype "passive"))
    )
    (net (code "185") (name "Net-(R192-Pad1)") (class "Default")
      (node (ref "R192") (pin "1") (pinfunction "1_1") (pintype "passive"))
      (node (ref "R193") (pin "2") (pinfunction "2_2") (pintype "passive"))
    )
    (net (code "186") (name "Net-(R193-Pad1)") (class "Default")
      (node (ref "R193") (pin "1") (pinfunction "1_1") (pintype "passive"))
      (node (ref "R194") (pin "2") (pinfunction "2_2") (pintype "passive"))
    )
    (net (code "187") (name "Net-(R194-Pad1)") (class "Default")
      (node (ref "R194") (pin "1") (pinfunction "1_1") (pintype "passive"))
      (node (ref "R195") (pin "2") (pinfunction "2_2") (pintype "passive"))
    )
    (net (code "188") (name "Net-(R195-Pad1)") (class "Default")
      (node (ref "R195") (pin "1") (pinfunction "1_1") (pintype "passive"))
      (node (ref "R196") (pin "2") (pinfunction "2_2") (pintype "passive"))
    )
    (net (code "189") (name "Net-(R204-Pad2)") (class "Default")
      (node (ref "R204") (pin "2") (pinfunction "2_2") (pintype "passive"))
      (node (ref "R205") (pin "1") (pinfunction "1_1") (pintype "passive"))
    )
    (net (code "190") (name "Net-(R205-Pad2)") (class "Default")
      (node (ref "R205") (pin "2") (pinfunction "2_2") (pintype "passive"))
      (node (ref "R206") (pin "1") (pinfunction "1_1") (pintype "passive"))
    )
    (net (code "191") (name "Net-(R207-Pad1)") (class "Default")
      (node (ref "R207") (pin "1") (pinfunction "1_1") (pintype "passive"))
      (node (ref "R208") (pin "2") (pinfunction "2_2") (pintype "passive"))
    )
    (net (code "192") (name "Net-(R208-Pad1)") (class "Default")
      (node (ref "R208") (pin "1") (pinfunction "1_1") (pintype "passive"))
      (node (ref "R209") (pin "1") (pinfunction "1_1") (pintype "passive"))
    )
    (net (code "193") (name "Net-(T1-B)") (class "Default")
      (node (ref "C9") (pin "2") (pinfunction "2_2") (pintype "passive"))
      (node (ref "R12") (pin "1") (pinfunction "1_1") (pintype "passive"))
      (node (ref "T1") (pin "2") (pinfunction "B_2") (pintype "passive"))
    )
    (net (code "194") (name "Net-(T1-C)") (class "Default")
      (node (ref "C9") (pin "1") (pinfunction "1_1") (pintype "passive"))
      (node (ref "R15") (pin "1") (pinfunction "1_1") (pintype "passive"))
      (node (ref "T1") (pin "3") (pinfunction "C_3") (pintype "passive"))
      (node (ref "T2") (pin "2") (pinfunction "B_2") (pintype "passive"))
    )
    (net (code "195") (name "Net-(T2-E)") (class "Default")
      (node (ref "R12") (pin "2") (pinfunction "2_2") (pintype "passive"))
      (node (ref "R28") (pin "1") (pinfunction "1_1") (pintype "passive"))
      (node (ref "T2") (pin "1") (pinfunction "E_1") (pintype "passive"))
    )
    (net (code "196") (name "Net-(U$1-CC1)") (class "Default")
      (node (ref "C10") (pin "1") (pinfunction "1_1") (pintype "passive"))
      (node (ref "U$1") (pin "P$3") (pinfunction "CC1_P$3") (pintype "bidirectional"))
    )
    (net (code "197") (name "Net-(U$1-CC2)") (class "Default")
      (node (ref "C10") (pin "2") (pinfunction "2_2") (pintype "passive"))
      (node (ref "U$1") (pin "P$4") (pinfunction "CC2_P$4") (pintype "bidirectional"))
    )
    (net (code "198") (name "Net-(U$2-CC1)") (class "Default")
      (node (ref "C12") (pin "1") (pinfunction "1_1") (pintype "passive"))
      (node (ref "U$2") (pin "P$3") (pinfunction "CC1_P$3") (pintype "bidirectional"))
    )
    (net (code "199") (name "Net-(U$2-CC2)") (class "Default")
      (node (ref "C12") (pin "2") (pinfunction "2_2") (pintype "passive"))
      (node (ref "U$2") (pin "P$4") (pinfunction "CC2_P$4") (pintype "bidirectional"))
    )
    (net (code "200") (name "Net-(U$3-CC1)") (class "Default")
      (node (ref "C14") (pin "1") (pinfunction "1_1") (pintype "passive"))
      (node (ref "U$3") (pin "P$3") (pinfunction "CC1_P$3") (pintype "bidirectional"))
    )
    (net (code "201") (name "Net-(U$3-CC2)") (class "Default")
      (node (ref "C14") (pin "2") (pinfunction "2_2") (pintype "passive"))
      (node (ref "U$3") (pin "P$4") (pinfunction "CC2_P$4") (pintype "bidirectional"))
    )
    (net (code "202") (name "Net-(U$4-CC1)") (class "Default")
      (node (ref "C5") (pin "1") (pinfunction "1_1") (pintype "passive"))
      (node (ref "U$4") (pin "P$3") (pinfunction "CC1_P$3") (pintype "bidirectional"))
    )
    (net (code "203") (name "Net-(U$4-CC2)") (class "Default")
      (node (ref "C5") (pin "2") (pinfunction "2_2") (pintype "passive"))
      (node (ref "U$4") (pin "P$4") (pinfunction "CC2_P$4") (pintype "bidirectional"))
    )
    (net (code "204") (name "Net-(U$4-OUT)") (class "Default")
      (node (ref "C7") (pin "2") (pinfunction "2_2") (pintype "passive"))
      (node (ref "D8") (pin "A") (pinfunction "A_A") (pintype "passive"))
      (node (ref "OUT") (pin "P$1") (pinfunction "P$1_P$1") (pintype "bidirectional"))
      (node (ref "R21") (pin "2") (pinfunction "2_2") (pintype "passive"))
      (node (ref "R3") (pin "2") (pinfunction "2_2") (pintype "passive"))
      (node (ref "U$4") (pin "P$5") (pinfunction "OUT_P$5") (pintype "output"))
    )
    (net (code "205") (name "Net-(U$5-CC1)") (class "Default")
      (node (ref "C16") (pin "1") (pinfunction "1_1") (pintype "passive"))
      (node (ref "U$5") (pin "P$3") (pinfunction "CC1_P$3") (pintype "bidirectional"))
    )
    (net (code "206") (name "Net-(U$5-CC2)") (class "Default")
      (node (ref "C16") (pin "2") (pinfunction "2_2") (pintype "passive"))
      (node (ref "U$5") (pin "P$4") (pinfunction "CC2_P$4") (pintype "bidirectional"))
    )
    (net (code "207") (name "Net-(U$6-CC1)") (class "Default")
      (node (ref "C18") (pin "1") (pinfunction "1_1") (pintype "passive"))
      (node (ref "U$6") (pin "P$3") (pinfunction "CC1_P$3") (pintype "bidirectional"))
    )
    (net (code "208") (name "Net-(U$6-CC2)") (class "Default")
      (node (ref "C18") (pin "2") (pinfunction "2_2") (pintype "passive"))
      (node (ref "U$6") (pin "P$4") (pinfunction "CC2_P$4") (pintype "bidirectional"))
    )
    (net (code "209") (name "Net-(U$7-CC1)") (class "Default")
      (node (ref "C20") (pin "1") (pinfunction "1_1") (pintype "passive"))
      (node (ref "U$7") (pin "P$3") (pinfunction "CC1_P$3") (pintype "bidirectional"))
    )
    (net (code "210") (name "Net-(U$7-CC2)") (class "Default")
      (node (ref "C20") (pin "2") (pinfunction "2_2") (pintype "passive"))
      (node (ref "U$7") (pin "P$4") (pinfunction "CC2_P$4") (pintype "bidirectional"))
    )
    (net (code "211") (name "Net-(U$8-CC1)") (class "Default")
      (node (ref "C22") (pin "1") (pinfunction "1_1") (pintype "passive"))
      (node (ref "U$8") (pin "P$3") (pinfunction "CC1_P$3") (pintype "bidirectional"))
    )
    (net (code "212") (name "Net-(U$8-CC2)") (class "Default")
      (node (ref "C22") (pin "2") (pinfunction "2_2") (pintype "passive"))
      (node (ref "U$8") (pin "P$4") (pinfunction "CC2_P$4") (pintype "bidirectional"))
    )
    (net (code "213") (name "V+") (class "Default")
      (node (ref "C3") (pin "1") (pinfunction "1_1") (pintype "passive"))
      (node (ref "D2") (pin "C") (pinfunction "C_C") (pintype "passive"))
      (node (ref "HVIN") (pin "P$4") (pinfunction "S_P$4") (pintype "passive"))
      (node (ref "Q2") (pin "3") (pinfunction "E_3") (pintype "passive"))
      (node (ref "R8") (pin "1") (pinfunction "1_1") (pintype "passive"))
    )
    (net (code "214") (name "V-") (class "Default")
      (node (ref "C4") (pin "1") (pinfunction "1_1") (pintype "passive"))
      (node (ref "D3") (pin "A") (pinfunction "A_A") (pintype "passive"))
      (node (ref "HVIN") (pin "P$3") (pinfunction "S_P$3") (pintype "passive"))
      (node (ref "R30") (pin "2") (pinfunction "2_2") (pintype "passive"))
      (node (ref "T1") (pin "1") (pinfunction "E_1") (pintype "passive"))
    )
    (net (code "215") (name "unconnected-(J23B-S-PadP$2)") (class "Default")
      (node (ref "J23") (pin "P$2") (pinfunction "S_P$2") (pintype "passive"))
    )
  )
)
